# Sch1.net
KiCad netlist of a schematic drawn in EasyEDA Pro
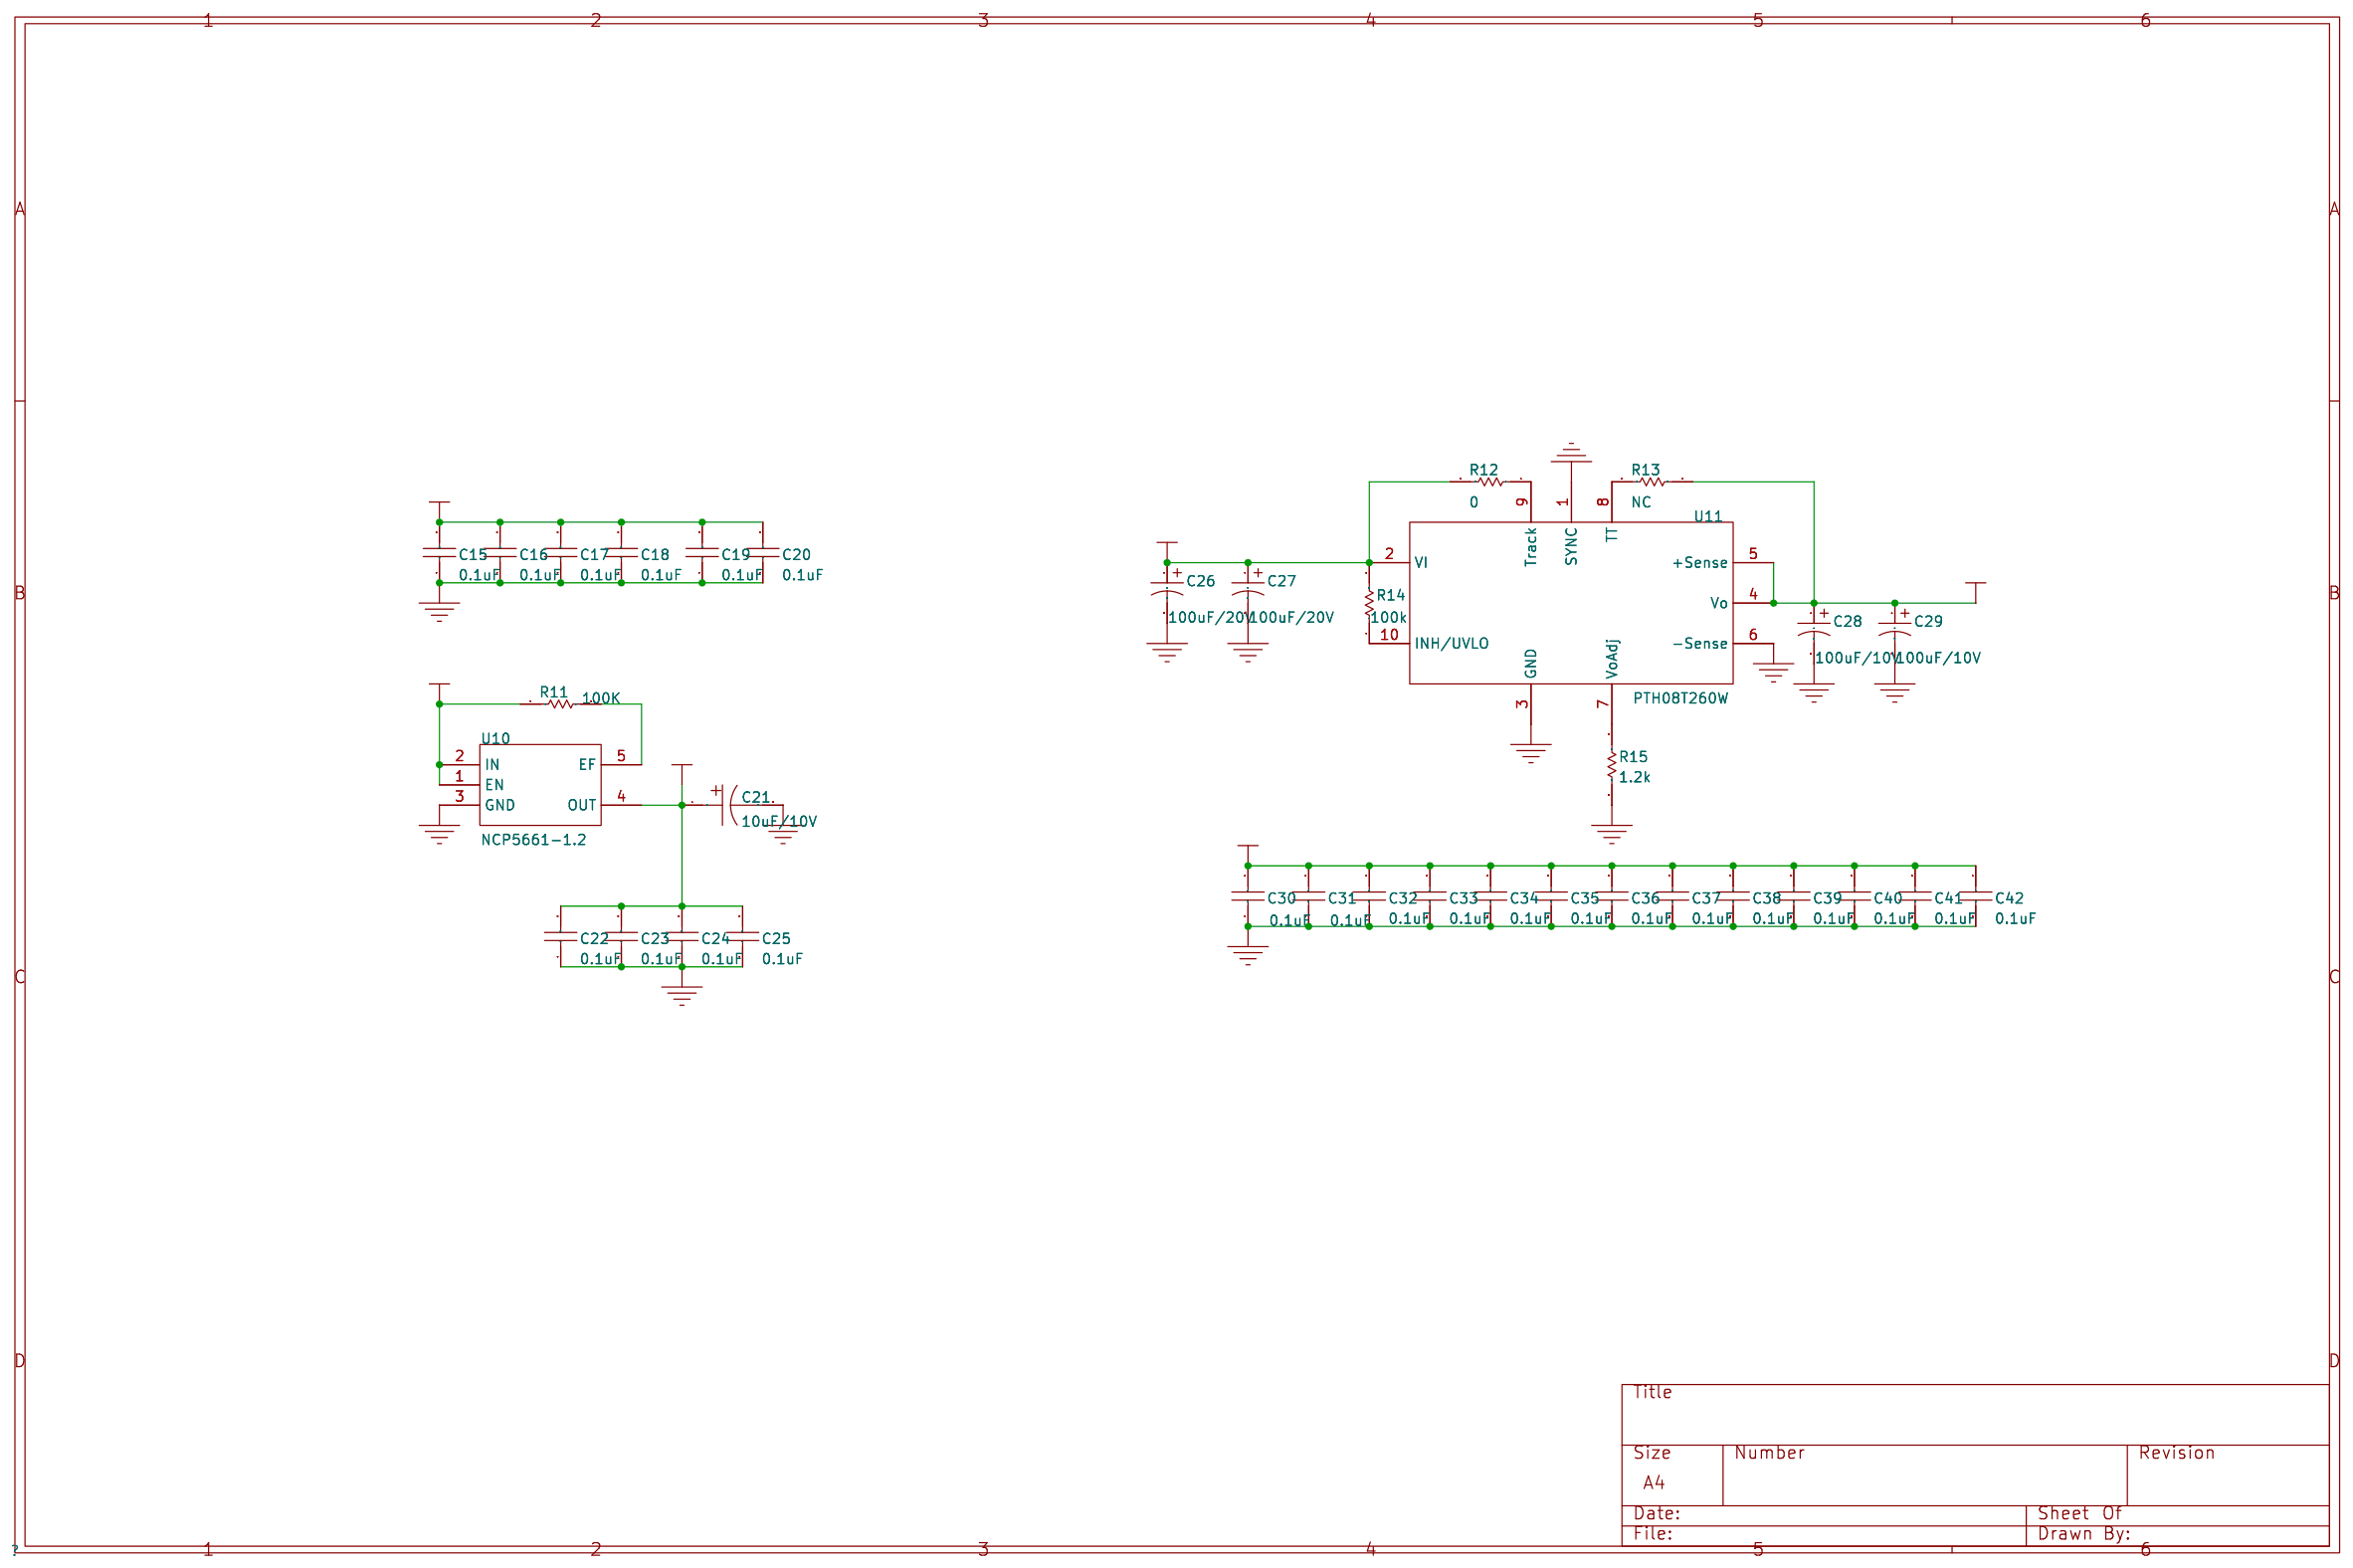
[diagram p0: 01-POWER]
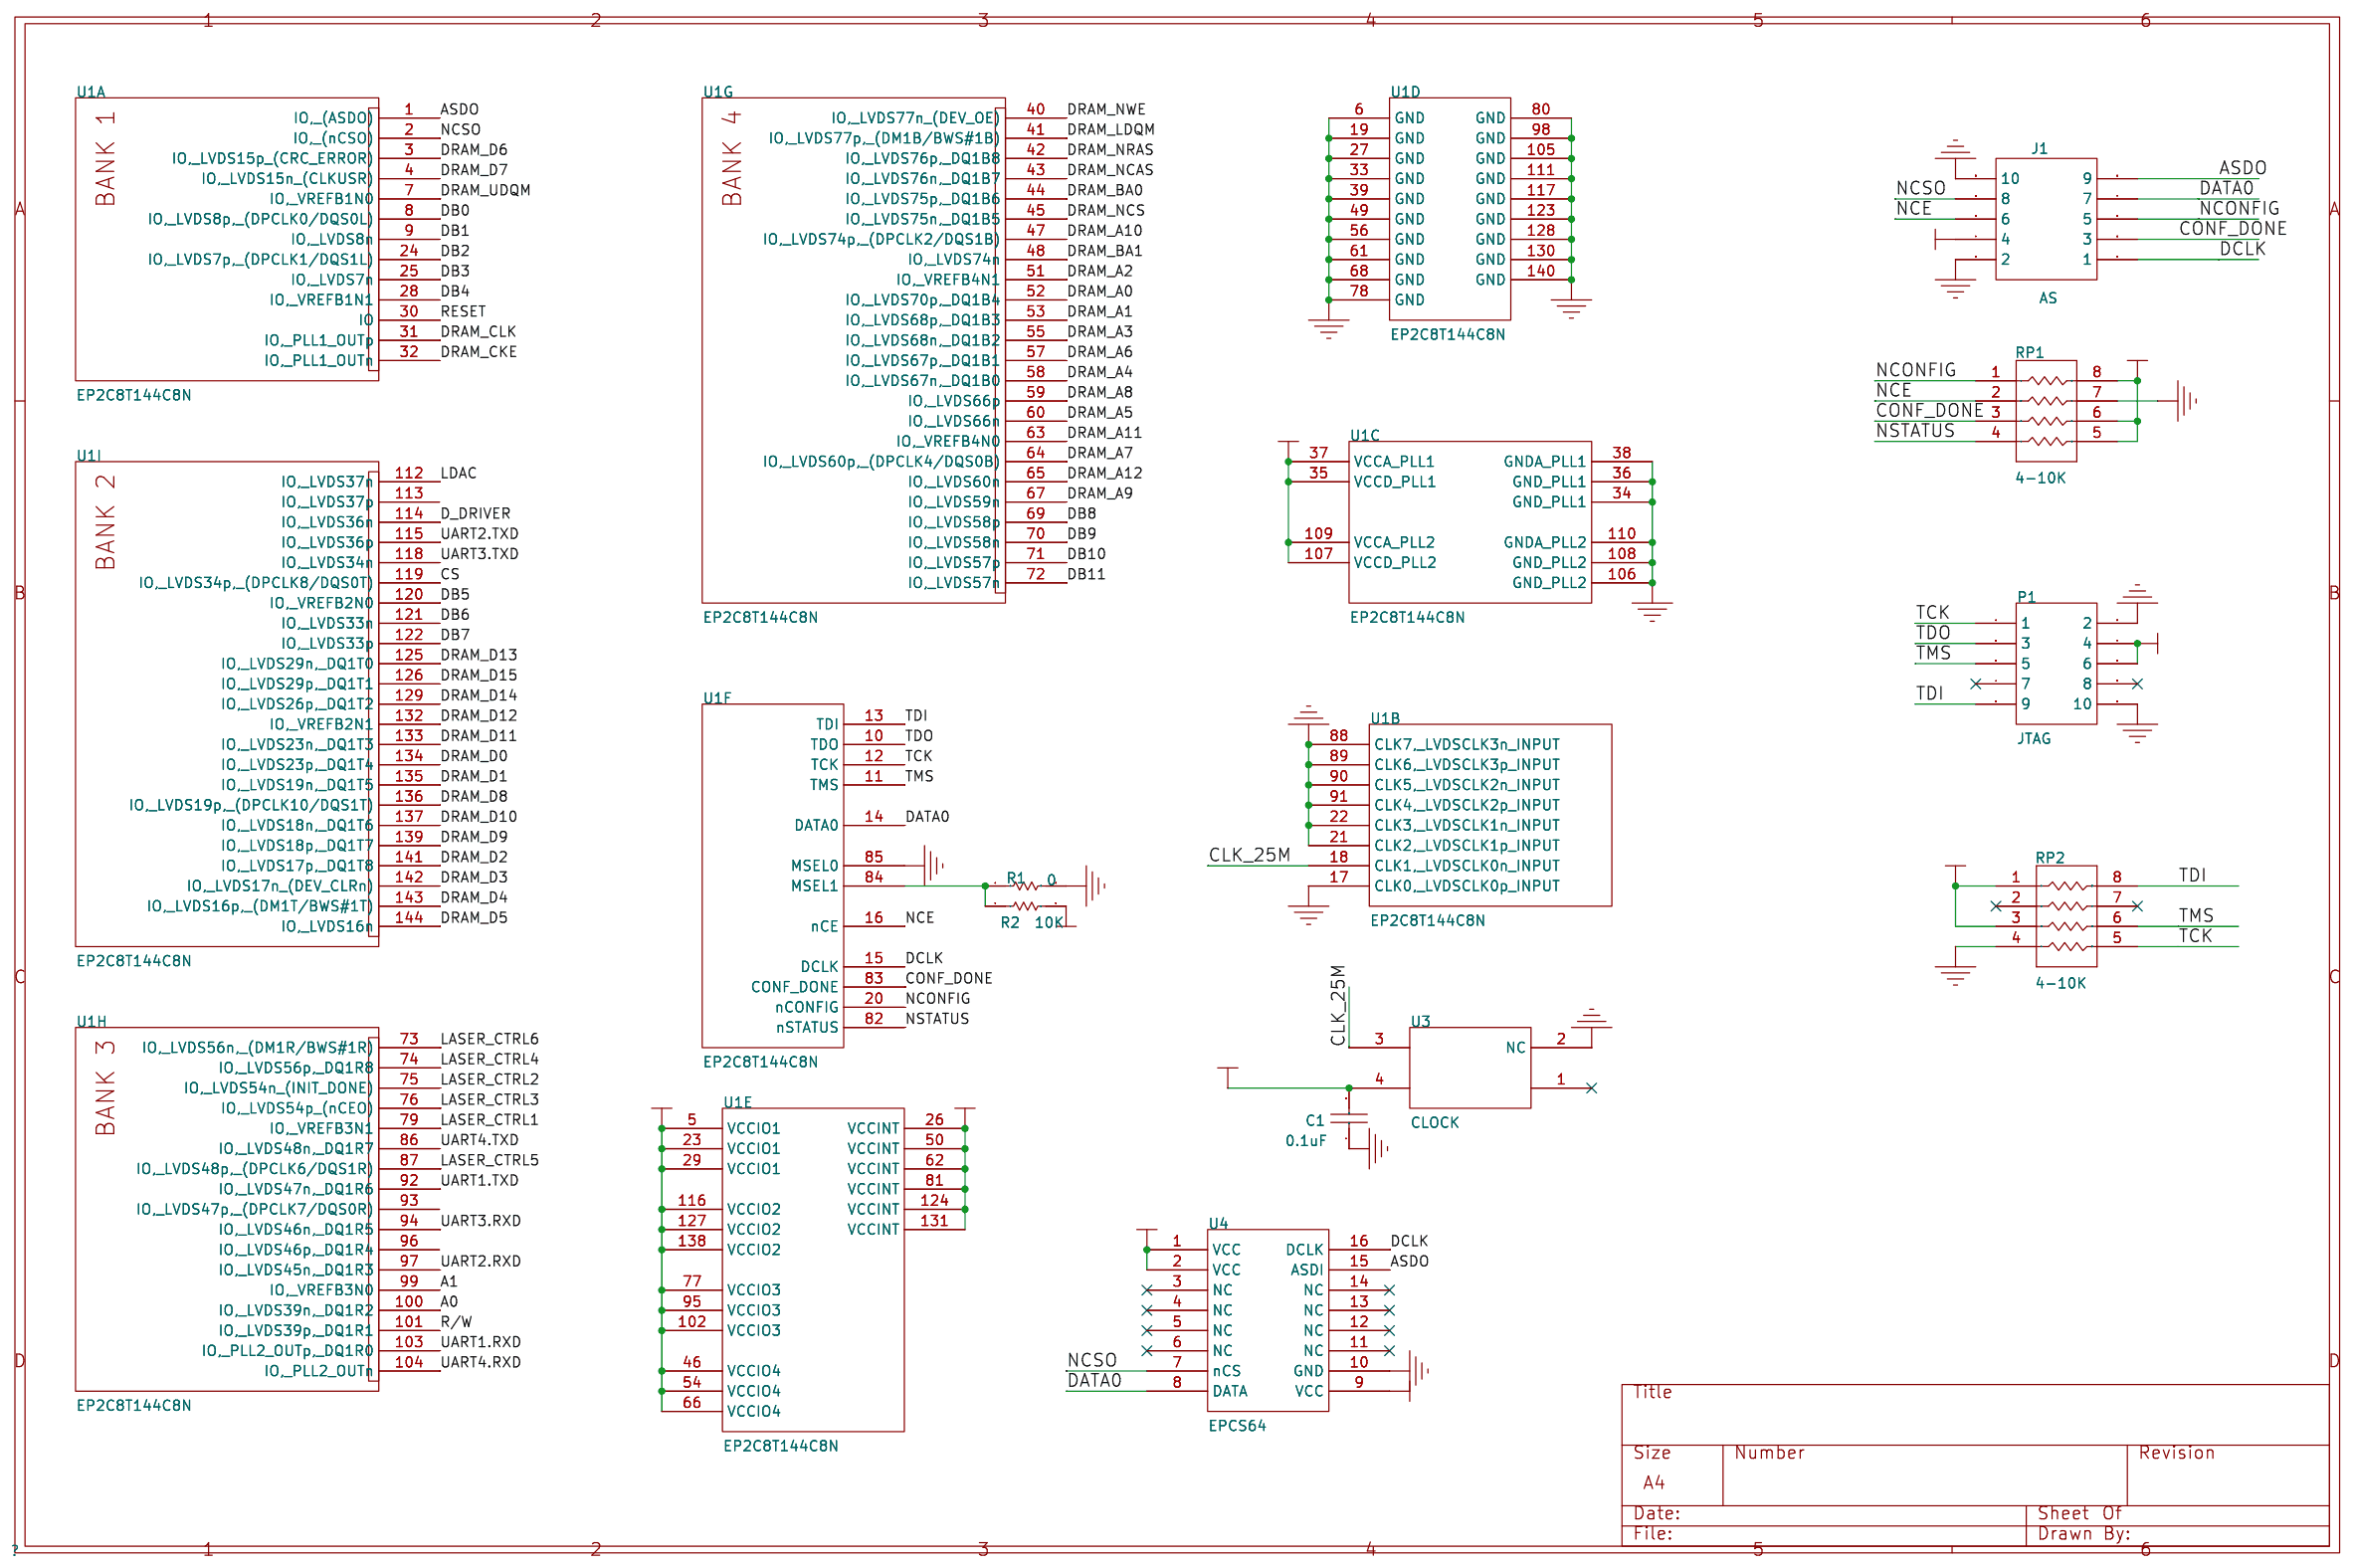
[diagram p1: 02-FPGA]
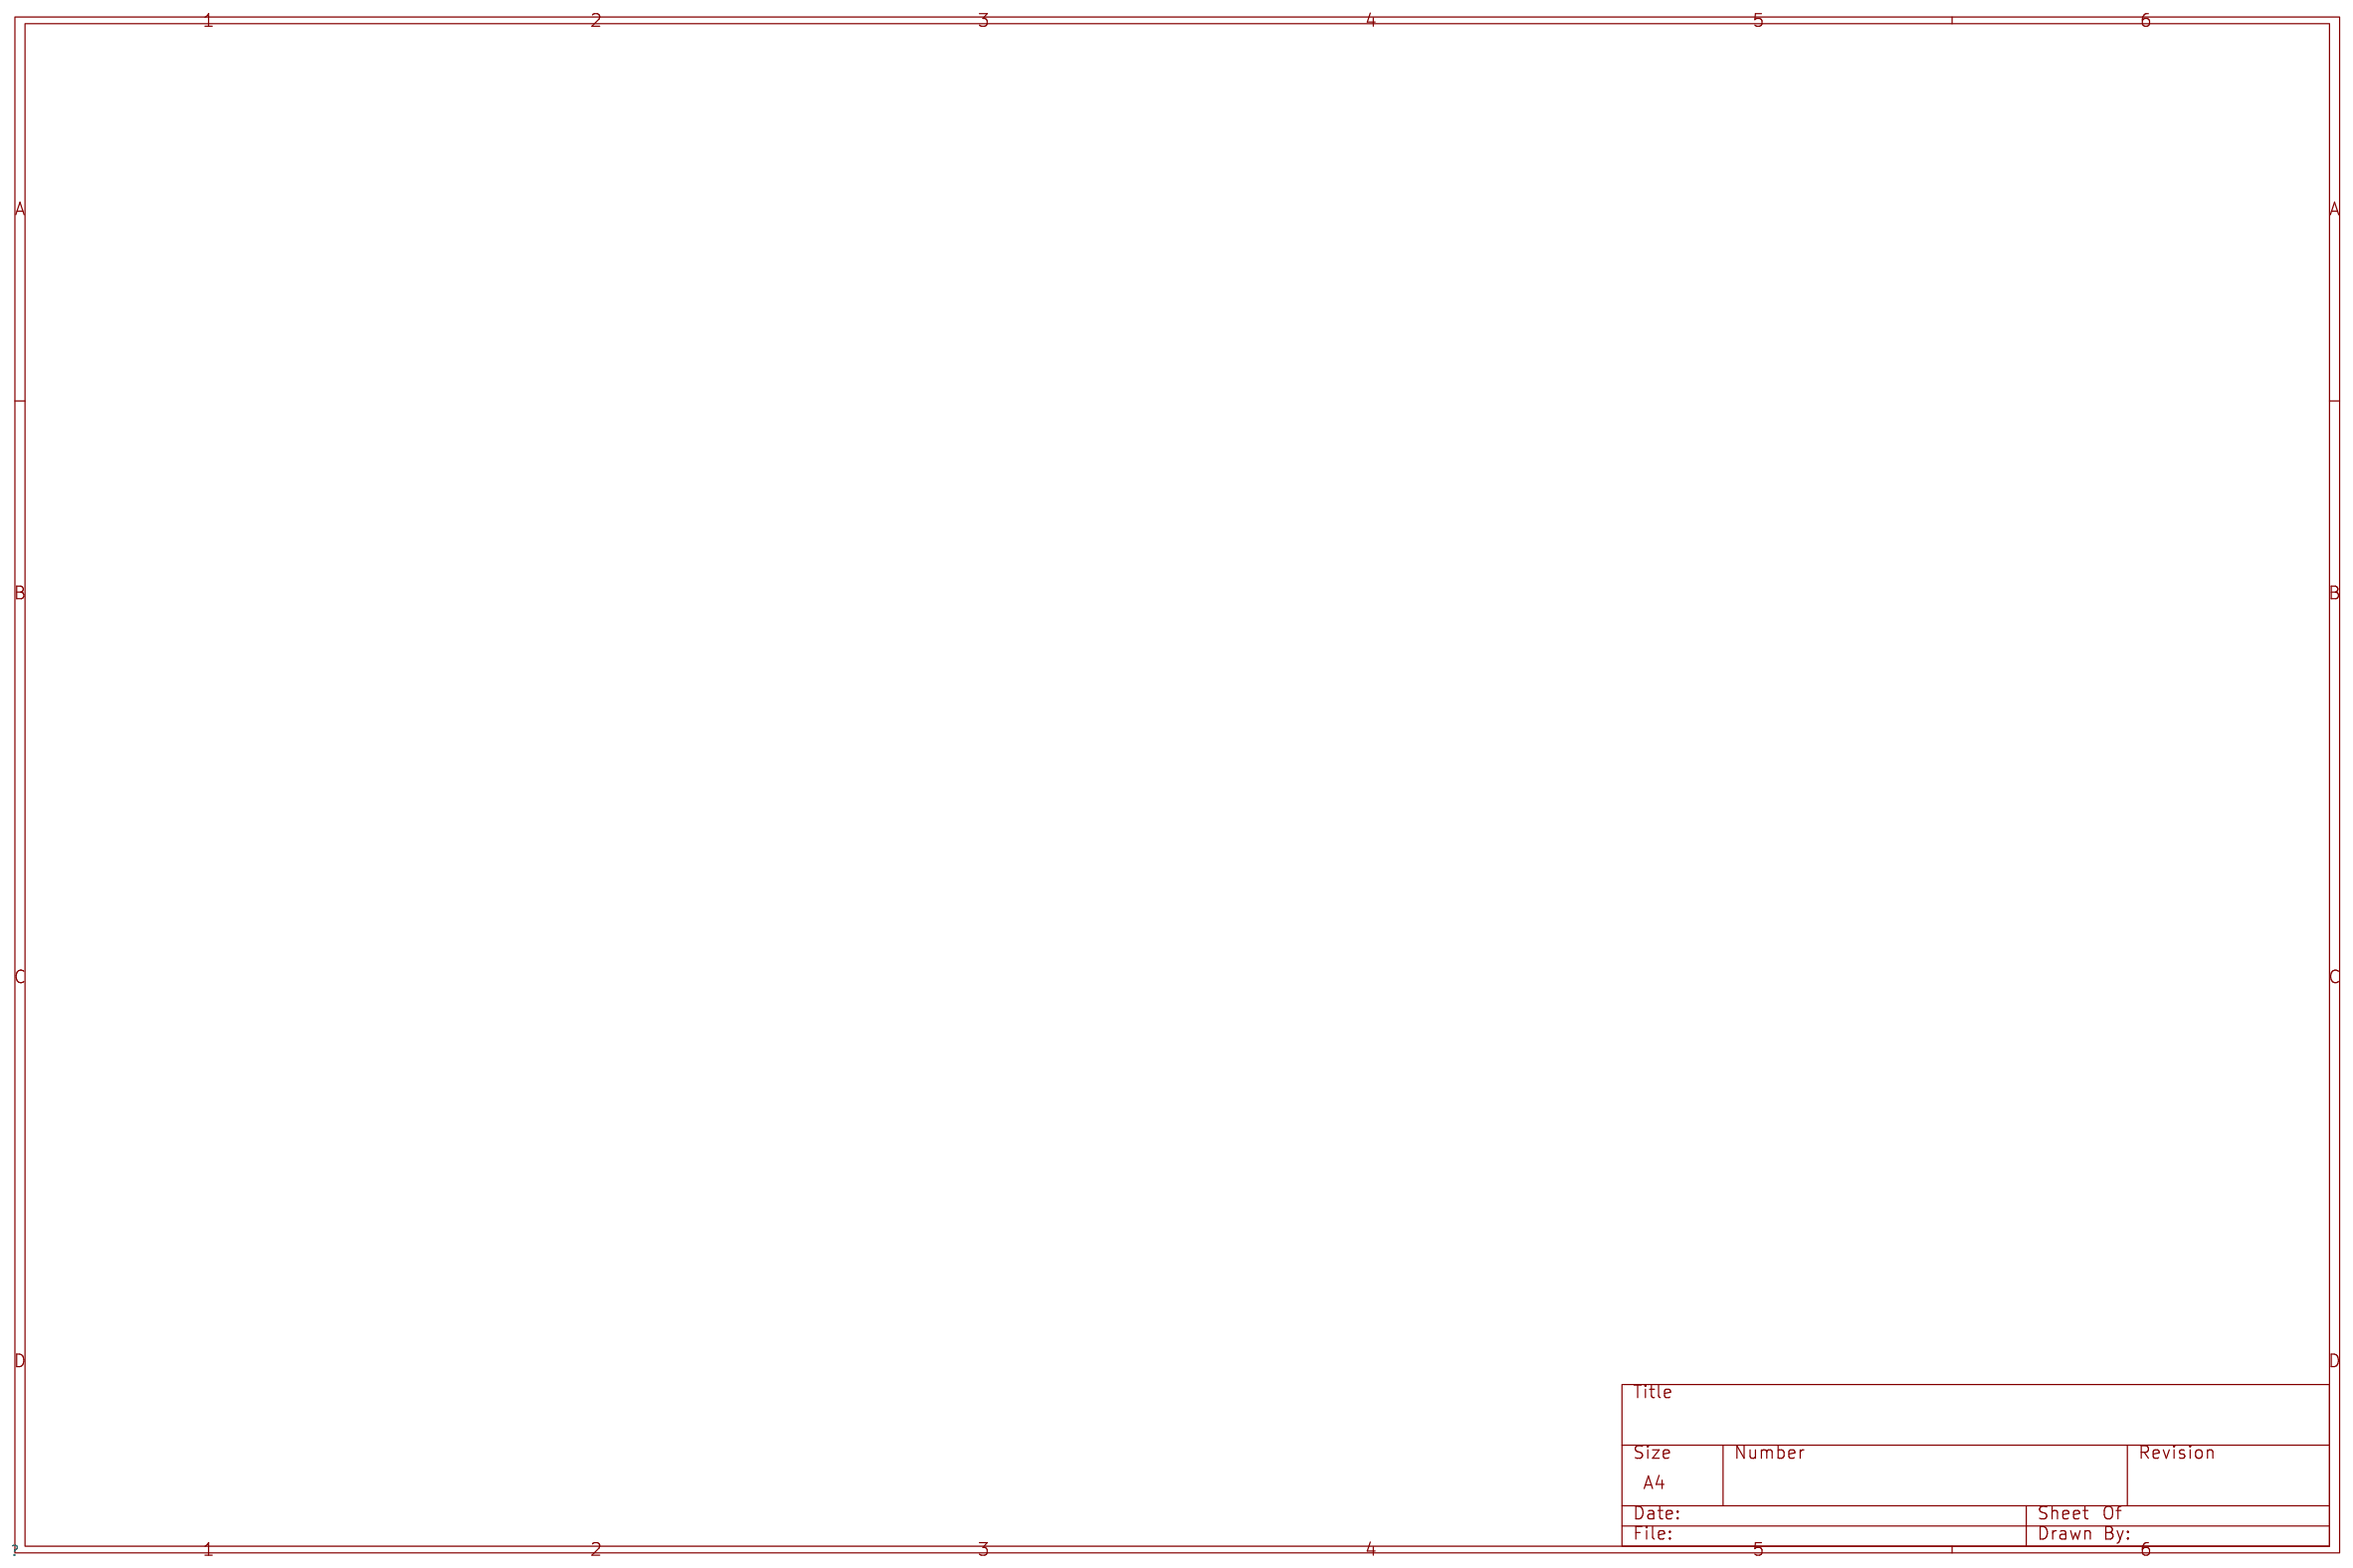
[diagram p2: 03-MEMORY]
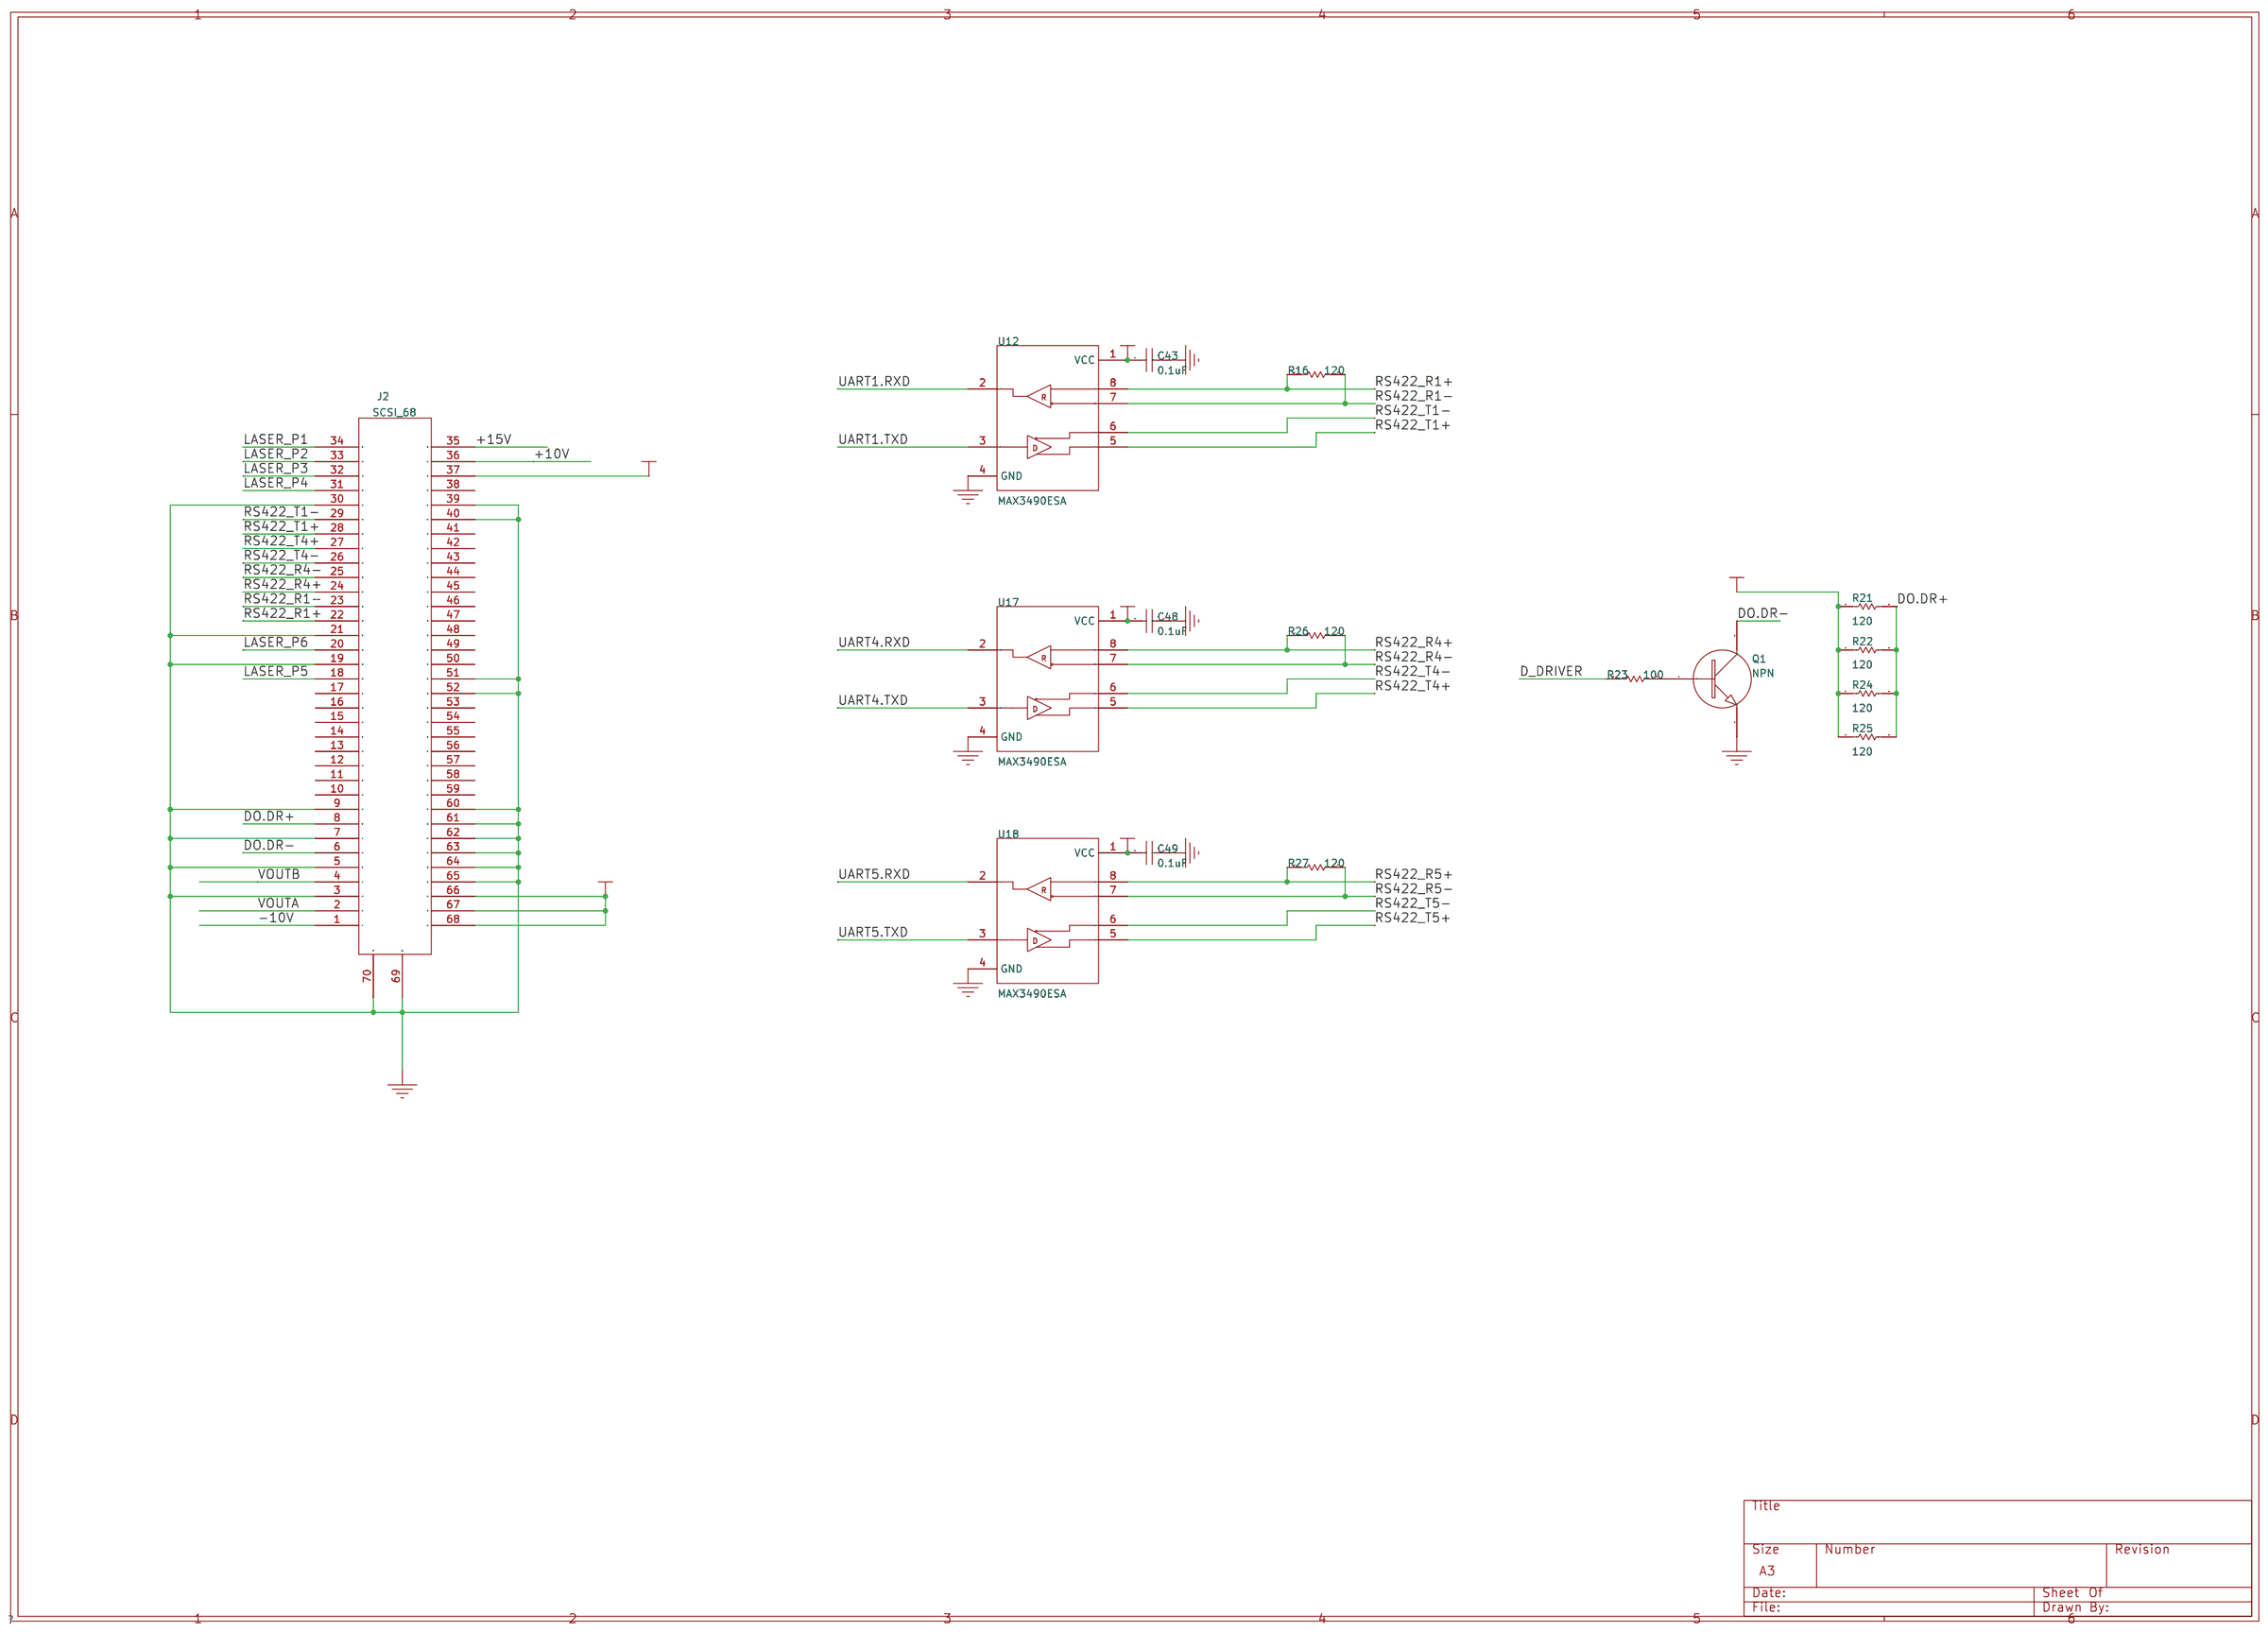
[diagram p3: 04-RS422-2]
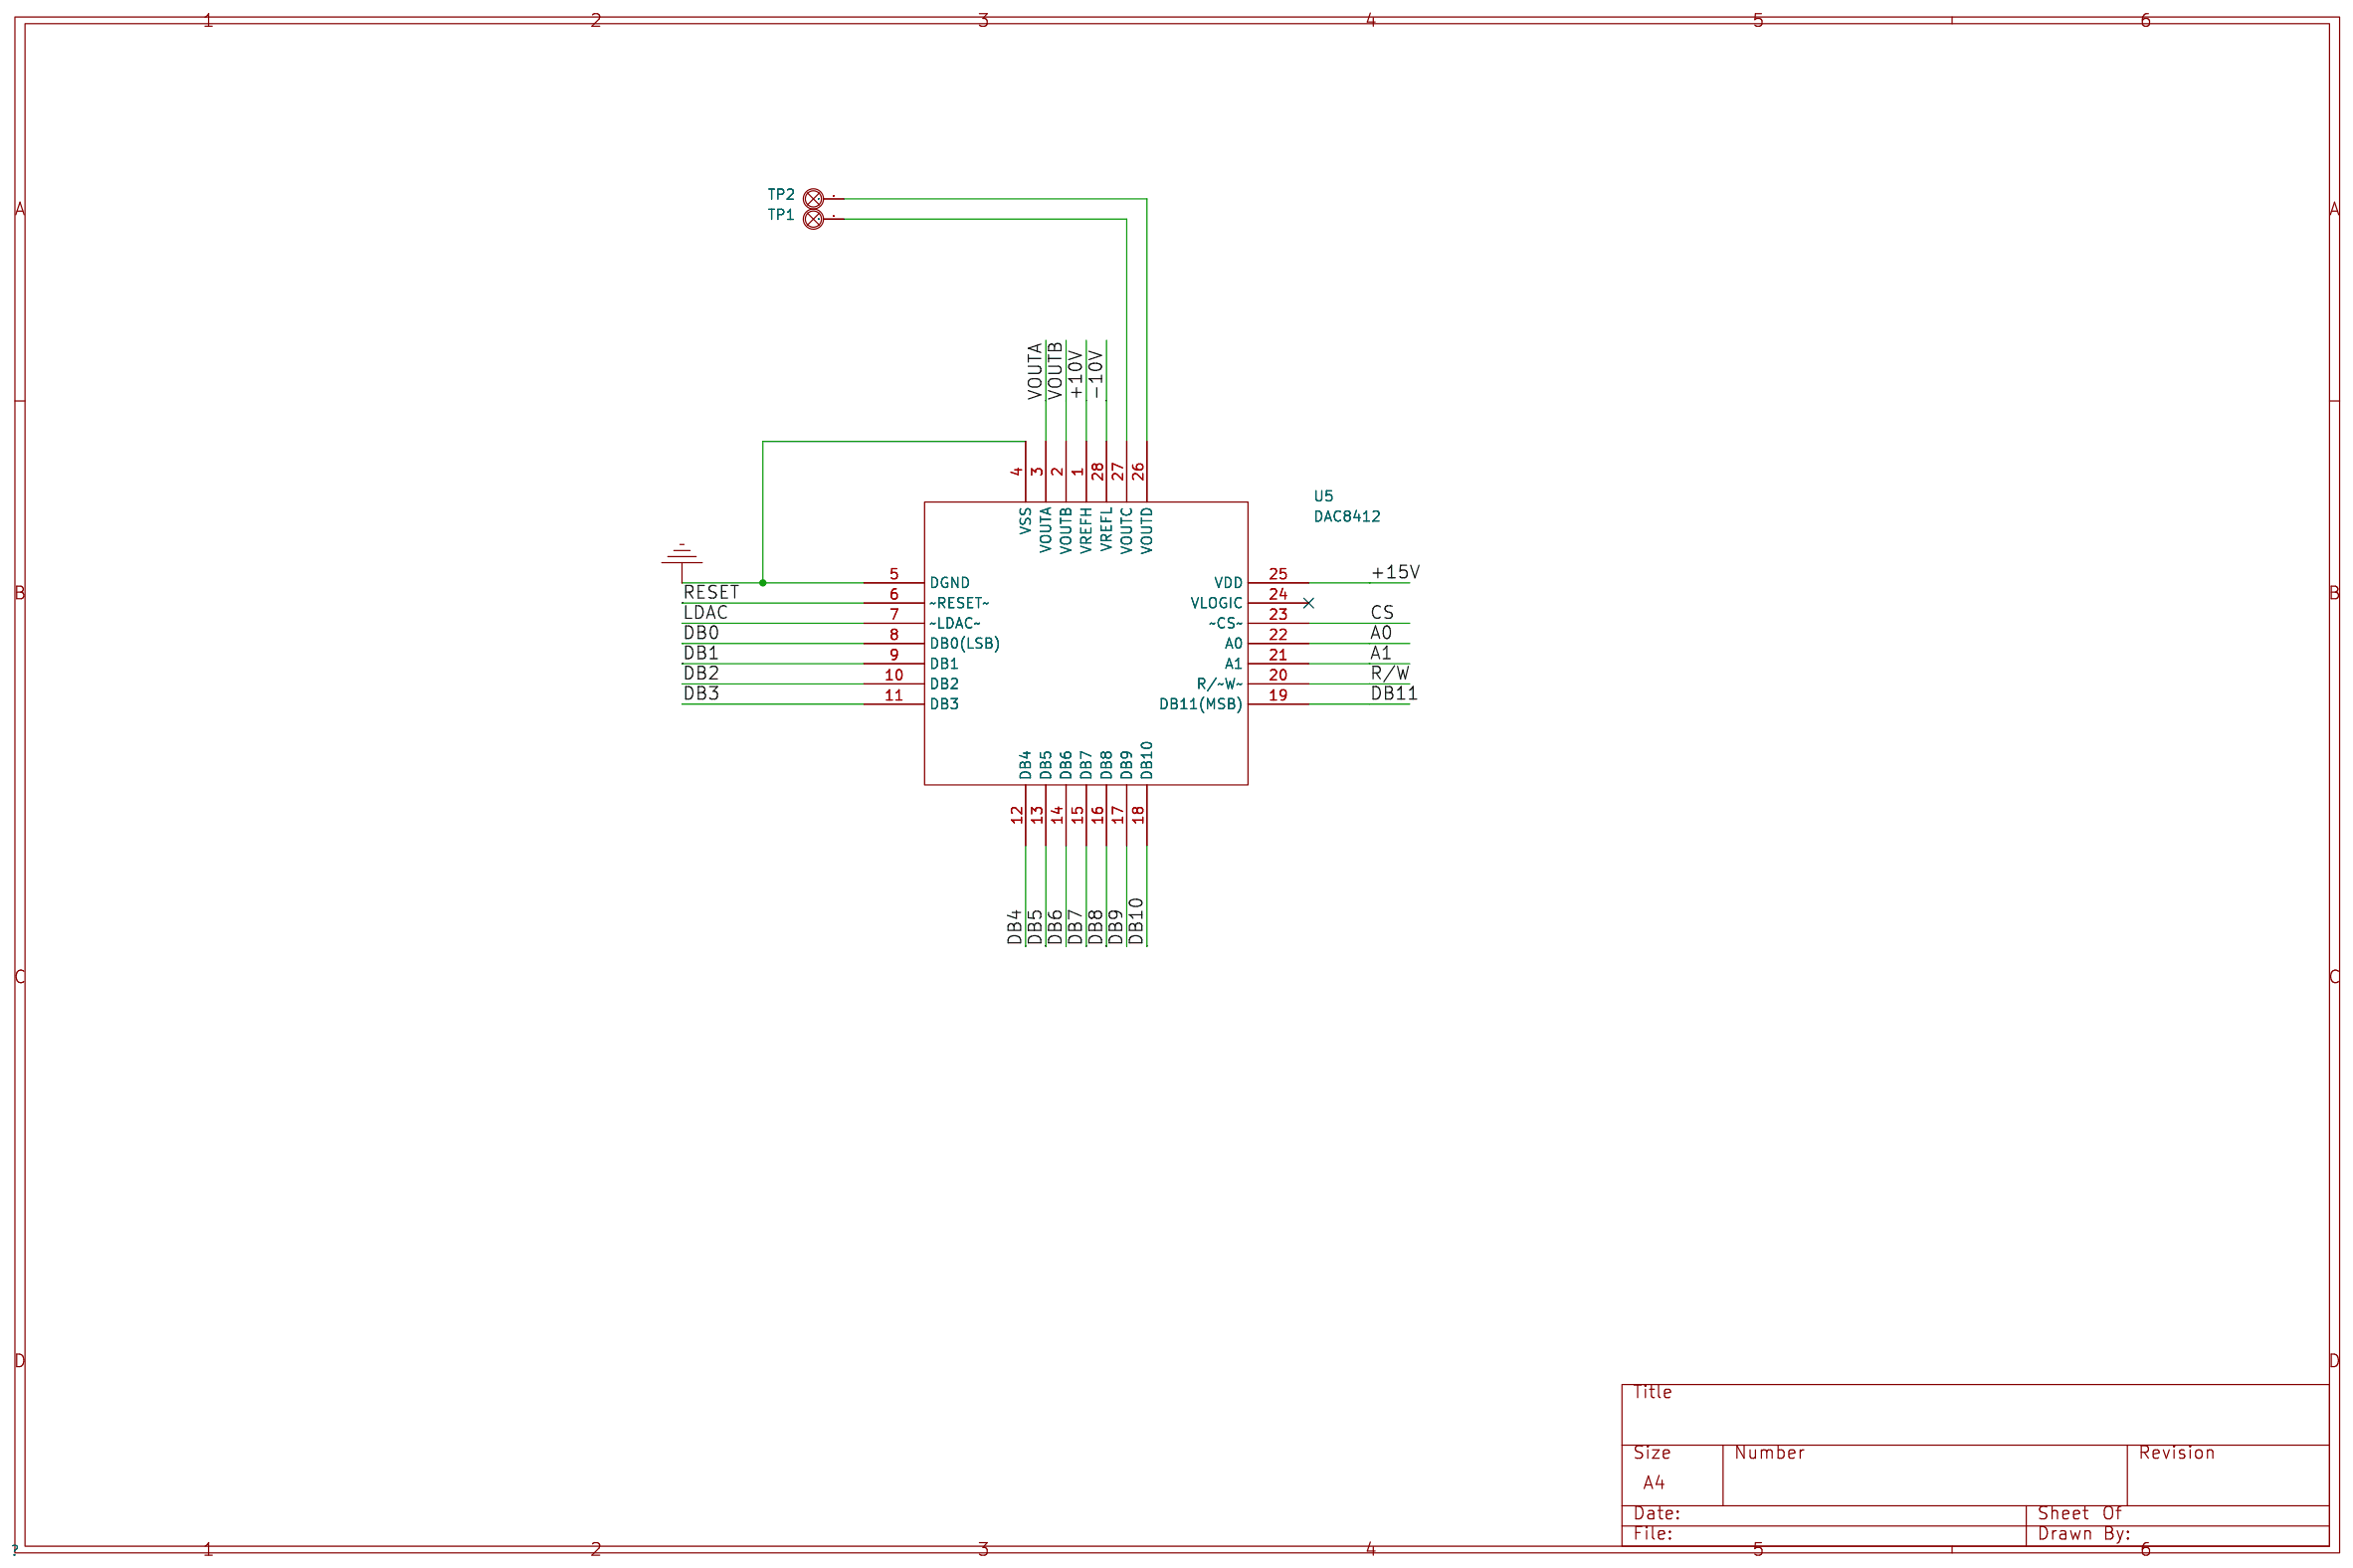
[diagram p4: 05-AD8412]
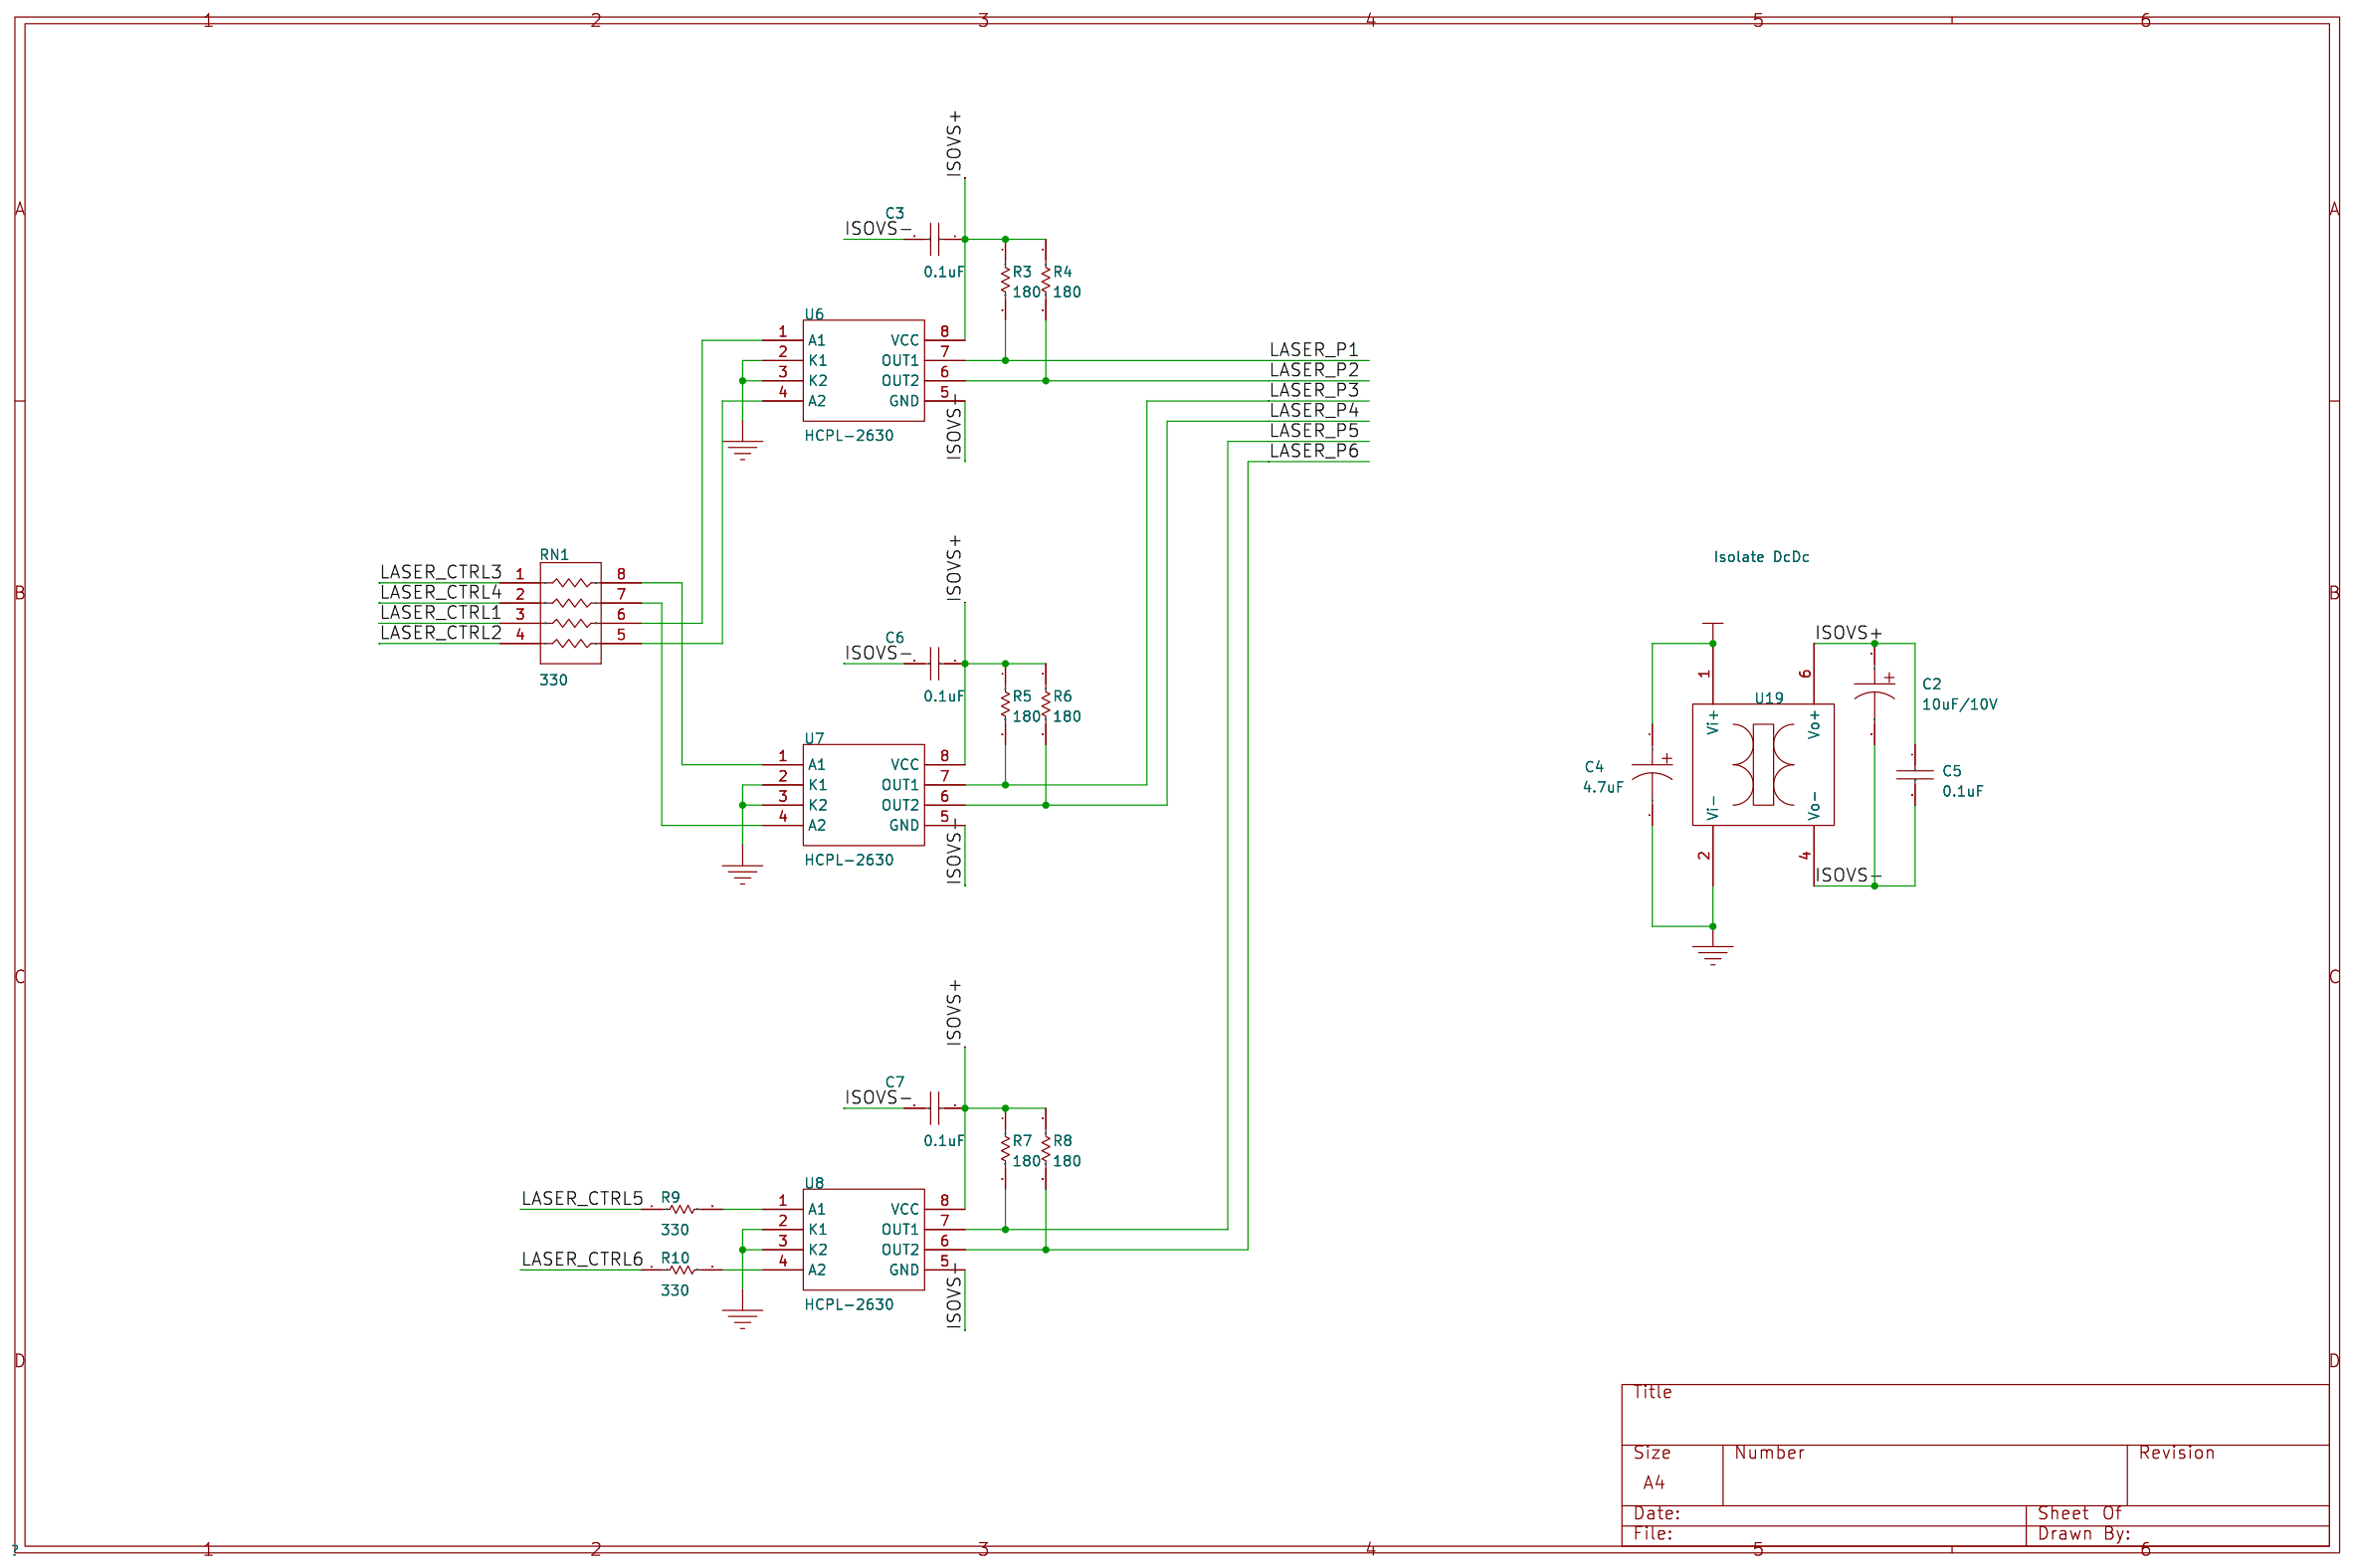
[diagram p5: 06-LASERCONTROL]

(export (version "E")
  (design (tool "Eeschema 10.0.6"))
  (components
    (comp (ref "C15")
      (value "0.1uF")
      (description "Capacitor")
      (fields (field (name "Publisher") "Altium Limited"))
      (libsource (lib "easyedapro") (part "Cap"))
    )
    (comp (ref "C16")
      (value "100pF")
      (description "Capacitor")
      (fields (field (name "Publisher") "Altium Limited"))
      (libsource (lib "easyedapro") (part "Cap"))
    )
    (comp (ref "C17")
      (value "100pF")
      (description "Capacitor")
      (fields (field (name "Publisher") "Altium Limited"))
      (libsource (lib "easyedapro") (part "Cap"))
    )
    (comp (ref "C18")
      (value "100pF")
      (description "Capacitor")
      (fields (field (name "Publisher") "Altium Limited"))
      (libsource (lib "easyedapro") (part "Cap"))
    )
    (comp (ref "C19")
      (value "100pF")
      (description "Capacitor")
      (fields (field (name "Publisher") "Altium Limited"))
      (libsource (lib "easyedapro") (part "Cap"))
    )
    (comp (ref "C20")
      (value "100pF")
      (description "Capacitor")
      (fields (field (name "Publisher") "Altium Limited"))
      (libsource (lib "easyedapro") (part "Cap"))
    )
    (comp (ref "C21")
      (value "10uF/10V")
      (description "Capacitor")
      (libsource (lib "easyedapro") (part "CAPACITOR POL"))
    )
    (comp (ref "C22")
      (value "0.1uF")
      (description "Capacitor (Semiconductor SIM Model)")
      (fields (field (name "Publisher") "Altium Limited"))
      (libsource (lib "easyedapro") (part "Cap Semi"))
    )
    (comp (ref "C23")
      (value "0.1uF")
      (description "Capacitor (Semiconductor SIM Model)")
      (fields (field (name "Publisher") "Altium Limited"))
      (libsource (lib "easyedapro") (part "Cap Semi"))
    )
    (comp (ref "C24")
      (value "0.1uF")
      (description "Capacitor (Semiconductor SIM Model)")
      (fields (field (name "Publisher") "Altium Limited"))
      (libsource (lib "easyedapro") (part "Cap Semi"))
    )
    (comp (ref "C25")
      (value "0.1uF")
      (description "Capacitor (Semiconductor SIM Model)")
      (fields (field (name "Publisher") "Altium Limited"))
      (libsource (lib "easyedapro") (part "Cap Semi"))
    )
    (comp (ref "C26")
      (value "100uF/20V")
      (description "钽电容,25V")
      (fields (field (name "Publisher") "Altium Limited"))
      (libsource (lib "easyedapro") (part "Cap Pol1"))
    )
    (comp (ref "C27")
      (value "100uF/20V")
      (description "钽电容,25V")
      (fields (field (name "Publisher") "Altium Limited"))
      (libsource (lib "easyedapro") (part "Cap Pol1"))
    )
    (comp (ref "C28")
      (value "100uF/10V")
      (description "10V, X7R")
      (fields (field (name "Publisher") "Altium Limited"))
      (libsource (lib "easyedapro") (part "Cap Pol1"))
    )
    (comp (ref "C29")
      (value "100uF/10V")
      (description "10V, X7R")
      (fields (field (name "Publisher") "Altium Limited"))
      (libsource (lib "easyedapro") (part "Cap Pol1"))
    )
    (comp (ref "C30")
      (value "0.1uF")
      (description "Capacitor (Semiconductor SIM Model)")
      (fields (field (name "Publisher") "Altium Limited"))
      (libsource (lib "easyedapro") (part "Cap Semi"))
    )
    (comp (ref "C31")
      (value "0.1uF")
      (description "Capacitor (Semiconductor SIM Model)")
      (fields (field (name "Publisher") "Altium Limited"))
      (libsource (lib "easyedapro") (part "Cap Semi"))
    )
    (comp (ref "C32")
      (value "0.1uF")
      (description "Capacitor (Semiconductor SIM Model)")
      (fields (field (name "Publisher") "Altium Limited"))
      (libsource (lib "easyedapro") (part "Cap Semi"))
    )
    (comp (ref "C33")
      (value "0.1uF")
      (description "Capacitor (Semiconductor SIM Model)")
      (fields (field (name "Publisher") "Altium Limited"))
      (libsource (lib "easyedapro") (part "Cap Semi"))
    )
    (comp (ref "C34")
      (value "0.1uF")
      (description "Capacitor (Semiconductor SIM Model)")
      (fields (field (name "Publisher") "Altium Limited"))
      (libsource (lib "easyedapro") (part "Cap Semi"))
    )
    (comp (ref "C35")
      (value "0.1uF")
      (description "Capacitor (Semiconductor SIM Model)")
      (fields (field (name "Publisher") "Altium Limited"))
      (libsource (lib "easyedapro") (part "Cap Semi"))
    )
    (comp (ref "C36")
      (value "0.1uF")
      (description "Capacitor (Semiconductor SIM Model)")
      (fields (field (name "Publisher") "Altium Limited"))
      (libsource (lib "easyedapro") (part "Cap Semi"))
    )
    (comp (ref "C37")
      (value "0.1uF")
      (description "Capacitor (Semiconductor SIM Model)")
      (fields (field (name "Publisher") "Altium Limited"))
      (libsource (lib "easyedapro") (part "Cap Semi"))
    )
    (comp (ref "C38")
      (value "0.1uF")
      (description "Capacitor (Semiconductor SIM Model)")
      (fields (field (name "Publisher") "Altium Limited"))
      (libsource (lib "easyedapro") (part "Cap Semi"))
    )
    (comp (ref "C39")
      (value "0.1uF")
      (description "Capacitor (Semiconductor SIM Model)")
      (fields (field (name "Publisher") "Altium Limited"))
      (libsource (lib "easyedapro") (part "Cap Semi"))
    )
    (comp (ref "C40")
      (value "0.1uF")
      (description "Capacitor (Semiconductor SIM Model)")
      (fields (field (name "Publisher") "Altium Limited"))
      (libsource (lib "easyedapro") (part "Cap Semi"))
    )
    (comp (ref "C41")
      (value "0.1uF")
      (description "Capacitor (Semiconductor SIM Model)")
      (fields (field (name "Publisher") "Altium Limited"))
      (libsource (lib "easyedapro") (part "Cap Semi"))
    )
    (comp (ref "C42")
      (value "0.1uF")
      (description "Capacitor (Semiconductor SIM Model)")
      (fields (field (name "Publisher") "Altium Limited"))
      (libsource (lib "easyedapro") (part "Cap Semi"))
    )
    (comp (ref "R11")
      (value "100K")
      (description "Semiconductor Resistor")
      (fields (field (name "Publisher") "Altium Limited"))
      (libsource (lib "easyedapro") (part "Res Semi"))
    )
    (comp (ref "R12")
      (value "0")
      (description "Resistor")
      (fields (field (name "Publisher") "Altium Limited"))
      (libsource (lib "easyedapro") (part "Res1"))
    )
    (comp (ref "R13")
      (value "NC")
      (description "Resistor")
      (fields (field (name "Publisher") "Altium Limited"))
      (libsource (lib "easyedapro") (part "Res1"))
    )
    (comp (ref "R14")
      (value "100k")
      (description "Resistor")
      (fields (field (name "Publisher") "Altium Limited"))
      (libsource (lib "easyedapro") (part "Res1"))
    )
    (comp (ref "R15")
      (value "1.2k")
      (description "Resistor")
      (fields (field (name "Publisher") "Altium Limited"))
      (libsource (lib "easyedapro") (part "Res1"))
    )
    (comp (ref "U10") (value "NCP5661-1.2") (libsource (lib "easyedapro") (part "NCP5661")))
    (comp (ref "U11")
      (value "PTH08T260W")
      (description "TI电源模块")
      (libsource (lib "easyedapro") (part "PTH08T230W"))
    )
    (comp (ref "C1") (value "0.1uF") (description "Capacitor") (libsource (lib "easyedapro") (part "CAP")))
    (comp (ref "J1") (value "AS") (libsource (lib "easyedapro") (part "HEADER 5X2")))
    (comp (ref "P1")
      (value "JTAG")
      (description "Header, 5-Pin, Dual row")
      (fields (field (name "Publisher") "Altium Limited"))
      (libsource (lib "easyedapro") (part "Header 5X2"))
    )
    (comp (ref "R1")
      (value "0")
      (description "Semiconductor Resistor")
      (fields (field (name "Publisher") "Altium Limited"))
      (libsource (lib "easyedapro") (part "Res Semi"))
    )
    (comp (ref "R2")
      (value "10K")
      (description "Semiconductor Resistor")
      (fields (field (name "Publisher") "Altium Limited"))
      (libsource (lib "easyedapro") (part "Res Semi"))
    )
    (comp (ref "RP1") (value "4-10K") (libsource (lib "easyedapro") (part "RES-4")))
    (comp (ref "RP2") (value "4-10K") (libsource (lib "easyedapro") (part "RES-4")))
    (comp (ref "U1")
      (value "EP2C8T144C8N")
      (fields (field (name "Publisher") "Altium Limited"))
      (libsource (lib "easyedapro") (part "EP2C8T144C8N"))
    )
    (comp (ref "U3") (value "CLOCK") (libsource (lib "easyedapro") (part "CLOCK")))
    (comp (ref "U4")
      (value "EPCS64")
      (description "EPCS16 64 128")
      (libsource (lib "easyedapro") (part "EPCS64"))
    )
    (comp (ref "C43")
      (value "0.1uF")
      (description "X7R")
      (fields (field (name "Publisher") "Altium Limited"))
      (libsource (lib "easyedapro") (part "Cap"))
    )
    (comp (ref "C48")
      (value "0.1uF")
      (description "X7R")
      (fields (field (name "Publisher") "Altium Limited"))
      (libsource (lib "easyedapro") (part "Cap"))
    )
    (comp (ref "C49")
      (value "0.1uF")
      (description "X7R")
      (fields (field (name "Publisher") "Altium Limited"))
      (libsource (lib "easyedapro") (part "Cap"))
    )
    (comp (ref "J2") (value "SCSI_68") (libsource (lib "easyedapro") (part "SCSI68")))
    (comp (ref "Q1") (value "NPN") (description "NPN Transistor") (libsource (lib "easyedapro") (part "NPN")))
    (comp (ref "R16")
      (value "120")
      (description "Resistor")
      (fields (field (name "Publisher") "Altium Limited"))
      (libsource (lib "easyedapro") (part "Res1"))
    )
    (comp (ref "R21")
      (value "120")
      (description "Resistor")
      (fields (field (name "Publisher") "Altium Limited"))
      (libsource (lib "easyedapro") (part "Res1"))
    )
    (comp (ref "R22")
      (value "120")
      (description "Resistor")
      (fields (field (name "Publisher") "Altium Limited"))
      (libsource (lib "easyedapro") (part "Res1"))
    )
    (comp (ref "R23")
      (value "100")
      (description "Resistor")
      (fields (field (name "Publisher") "Altium Limited"))
      (libsource (lib "easyedapro") (part "Res1"))
    )
    (comp (ref "R24")
      (value "120")
      (description "Resistor")
      (fields (field (name "Publisher") "Altium Limited"))
      (libsource (lib "easyedapro") (part "Res1"))
    )
    (comp (ref "R25")
      (value "120")
      (description "Resistor")
      (fields (field (name "Publisher") "Altium Limited"))
      (libsource (lib "easyedapro") (part "Res1"))
    )
    (comp (ref "R26")
      (value "120")
      (description "Resistor")
      (fields (field (name "Publisher") "Altium Limited"))
      (libsource (lib "easyedapro") (part "Res1"))
    )
    (comp (ref "R27")
      (value "120")
      (description "Resistor")
      (fields (field (name "Publisher") "Altium Limited"))
      (libsource (lib "easyedapro") (part "Res1"))
    )
    (comp (ref "U12")
      (value "MAX3490ESA")
      (description "Low-Power, Slew-Rate-Limited RS-485/RS-422 Transceiver")
      (fields (field (name "Publisher") "Altium Limited"))
      (libsource (lib "easyedapro") (part "MAX488ESA"))
    )
    (comp (ref "U17")
      (value "MAX3490ESA")
      (description "Low-Power, Slew-Rate-Limited RS-485/RS-422 Transceiver")
      (fields (field (name "Publisher") "Altium Limited"))
      (libsource (lib "easyedapro") (part "MAX488ESA"))
    )
    (comp (ref "U18")
      (value "MAX3490ESA")
      (description "Low-Power, Slew-Rate-Limited RS-485/RS-422 Transceiver")
      (fields (field (name "Publisher") "Altium Limited"))
      (libsource (lib "easyedapro") (part "MAX488ESA"))
    )
    (comp (ref "TP1") (value "TESTPOINT") (libsource (lib "easyedapro") (part "TESTPOINT_0")))
    (comp (ref "TP2") (value "TESTPOINT") (libsource (lib "easyedapro") (part "TESTPOINT_0")))
    (comp (ref "U5") (value "DAC8412") (libsource (lib "easyedapro") (part "DAC8412")))
    (comp (ref "C2")
      (value "10uF/10V")
      (description "Capacitor")
      (libsource (lib "easyedapro") (part "CAPACITOR POL"))
    )
    (comp (ref "C3")
      (value "100pF")
      (description "Capacitor")
      (fields (field (name "Publisher") "Altium Limited"))
      (libsource (lib "easyedapro") (part "Cap"))
    )
    (comp (ref "C4")
      (value "4.7uF")
      (description "Capacitor")
      (libsource (lib "easyedapro") (part "CAPACITOR POL"))
    )
    (comp (ref "C5") (value "0.1uF") (description "Capacitor") (libsource (lib "easyedapro") (part "CAP")))
    (comp (ref "C6")
      (value "100pF")
      (description "Capacitor")
      (fields (field (name "Publisher") "Altium Limited"))
      (libsource (lib "easyedapro") (part "Cap"))
    )
    (comp (ref "C7")
      (value "100pF")
      (description "Capacitor")
      (fields (field (name "Publisher") "Altium Limited"))
      (libsource (lib "easyedapro") (part "Cap"))
    )
    (comp (ref "R3")
      (value "1K")
      (description "Resistor")
      (fields (field (name "Publisher") "Altium Limited"))
      (libsource (lib "easyedapro") (part "Res1"))
    )
    (comp (ref "R4")
      (value "1K")
      (description "Resistor")
      (fields (field (name "Publisher") "Altium Limited"))
      (libsource (lib "easyedapro") (part "Res1"))
    )
    (comp (ref "R5")
      (value "1K")
      (description "Resistor")
      (fields (field (name "Publisher") "Altium Limited"))
      (libsource (lib "easyedapro") (part "Res1"))
    )
    (comp (ref "R6")
      (value "1K")
      (description "Resistor")
      (fields (field (name "Publisher") "Altium Limited"))
      (libsource (lib "easyedapro") (part "Res1"))
    )
    (comp (ref "R7")
      (value "1K")
      (description "Resistor")
      (fields (field (name "Publisher") "Altium Limited"))
      (libsource (lib "easyedapro") (part "Res1"))
    )
    (comp (ref "R8")
      (value "1K")
      (description "Resistor")
      (fields (field (name "Publisher") "Altium Limited"))
      (libsource (lib "easyedapro") (part "Res1"))
    )
    (comp (ref "R9")
      (value "1K")
      (description "Resistor")
      (fields (field (name "Publisher") "Altium Limited"))
      (libsource (lib "easyedapro") (part "Res1"))
    )
    (comp (ref "R10")
      (value "1K")
      (description "Resistor")
      (fields (field (name "Publisher") "Altium Limited"))
      (libsource (lib "easyedapro") (part "Res1"))
    )
    (comp (ref "RN1")
      (value "330")
      (description "Resistor Array,include 4 resistor in one chip")
      (libsource (lib "easyedapro") (part "RN4"))
    )
    (comp (ref "U6") (value "HCPL-2630") (libsource (lib "easyedapro") (part "HCPL-2630")))
    (comp (ref "U7") (value "HCPL-2630") (libsource (lib "easyedapro") (part "HCPL-2630")))
    (comp (ref "U8") (value "HCPL-2630") (libsource (lib "easyedapro") (part "HCPL-2630")))
    (comp (ref "U19") (value "Isolate DcDc") (libsource (lib "easyedapro") (part "MY_I_DC_DC")))
  )
  (nets
    (net (code "1") (name "+10V") (class "Default")
      (node (ref "J2") (pin "36") (pinfunction "36_36") (pintype "unspecified"))
      (node (ref "U5") (pin "1") (pinfunction "VREFH_1") (pintype "unspecified"))
    )
    (net (code "2") (name "+15V") (class "Default")
      (node (ref "J2") (pin "35") (pinfunction "35_35") (pintype "unspecified"))
      (node (ref "U5") (pin "25") (pinfunction "VDD_25") (pintype "unspecified"))
    )
    (net (code "3") (name "-10V") (class "Default")
      (node (ref "J2") (pin "1") (pinfunction "1_1") (pintype "unspecified"))
      (node (ref "U5") (pin "28") (pinfunction "VREFL_28") (pintype "unspecified"))
    )
    (net (code "4") (name "A0") (class "Default")
      (node (ref "U1") (pin "100") (pinfunction "IO,_LVDS39n,_DQ1R2_100") (pintype "bidirectional"))
      (node (ref "U5") (pin "22") (pinfunction "A0_22") (pintype "unspecified"))
    )
    (net (code "5") (name "A1") (class "Default")
      (node (ref "U1") (pin "99") (pinfunction "IO,_VREFB3N0_99") (pintype "bidirectional"))
      (node (ref "U5") (pin "21") (pinfunction "A1_21") (pintype "unspecified"))
    )
    (net (code "6") (name "ASDO") (class "Default")
      (node (ref "J1") (pin "9") (pinfunction "9_9") (pintype "unspecified"))
      (node (ref "U1") (pin "1") (pinfunction "IO,_(ASDO)_1") (pintype "bidirectional"))
      (node (ref "U4") (pin "15") (pinfunction "ASDI_15") (pintype "unspecified"))
    )
    (net (code "7") (name "CLK_25M") (class "Default")
      (node (ref "U1") (pin "18") (pinfunction "CLK1,_LVDSCLK0n_INPUT_18") (pintype "input"))
      (node (ref "U3") (pin "3") (pintype "unspecified"))
    )
    (net (code "8") (name "CONF_DONE") (class "Default")
      (node (ref "J1") (pin "3") (pinfunction "3_3") (pintype "unspecified"))
      (node (ref "RP1") (pin "3") (pinfunction "3_3") (pintype "unspecified"))
      (node (ref "U1") (pin "83") (pinfunction "CONF_DONE_83") (pintype "bidirectional"))
    )
    (net (code "9") (name "CS") (class "Default")
      (node (ref "U1") (pin "119") (pinfunction "IO,_LVDS34p,_(DPCLK8/DQS0T)_119") (pintype "bidirectional"))
      (node (ref "U5") (pin "23") (pinfunction "~CS~_23") (pintype "unspecified"))
    )
    (net (code "10") (name "DATA0") (class "Default")
      (node (ref "J1") (pin "7") (pinfunction "7_7") (pintype "unspecified"))
      (node (ref "U1") (pin "14") (pinfunction "DATA0_14") (pintype "input"))
      (node (ref "U4") (pin "8") (pinfunction "DATA_8") (pintype "unspecified"))
    )
    (net (code "11") (name "DB0") (class "Default")
      (node (ref "U1") (pin "8") (pinfunction "IO,_LVDS8p,_(DPCLK0/DQS0L)_8") (pintype "bidirectional"))
      (node (ref "U5") (pin "8") (pinfunction "DB0(LSB)_8") (pintype "unspecified"))
    )
    (net (code "12") (name "DB1") (class "Default")
      (node (ref "U1") (pin "9") (pinfunction "IO,_LVDS8n_9") (pintype "bidirectional"))
      (node (ref "U5") (pin "9") (pinfunction "DB1_9") (pintype "unspecified"))
    )
    (net (code "13") (name "DB2") (class "Default")
      (node (ref "U1") (pin "24") (pinfunction "IO,_LVDS7p,_(DPCLK1/DQS1L)_24") (pintype "bidirectional"))
      (node (ref "U5") (pin "10") (pinfunction "DB2_10") (pintype "unspecified"))
    )
    (net (code "14") (name "DB3") (class "Default")
      (node (ref "U1") (pin "25") (pinfunction "IO,_LVDS7n_25") (pintype "bidirectional"))
      (node (ref "U5") (pin "11") (pinfunction "DB3_11") (pintype "unspecified"))
    )
    (net (code "15") (name "DB4") (class "Default")
      (node (ref "U1") (pin "28") (pinfunction "IO,_VREFB1N1_28") (pintype "bidirectional"))
      (node (ref "U5") (pin "12") (pinfunction "DB4_12") (pintype "unspecified"))
    )
    (net (code "16") (name "DB5") (class "Default")
      (node (ref "U1") (pin "120") (pinfunction "IO,_VREFB2N0_120") (pintype "bidirectional"))
      (node (ref "U5") (pin "13") (pinfunction "DB5_13") (pintype "unspecified"))
    )
    (net (code "17") (name "DB6") (class "Default")
      (node (ref "U1") (pin "121") (pinfunction "IO,_LVDS33n_121") (pintype "bidirectional"))
      (node (ref "U5") (pin "14") (pinfunction "DB6_14") (pintype "unspecified"))
    )
    (net (code "18") (name "DB7") (class "Default")
      (node (ref "U1") (pin "122") (pinfunction "IO,_LVDS33p_122") (pintype "bidirectional"))
      (node (ref "U5") (pin "15") (pinfunction "DB7_15") (pintype "unspecified"))
    )
    (net (code "19") (name "DB8") (class "Default")
      (node (ref "U1") (pin "69") (pinfunction "IO,_LVDS58p_69") (pintype "bidirectional"))
      (node (ref "U5") (pin "16") (pinfunction "DB8_16") (pintype "unspecified"))
    )
    (net (code "20") (name "DB9") (class "Default")
      (node (ref "U1") (pin "70") (pinfunction "IO,_LVDS58n_70") (pintype "bidirectional"))
      (node (ref "U5") (pin "17") (pinfunction "DB9_17") (pintype "unspecified"))
    )
    (net (code "21") (name "DB10") (class "Default")
      (node (ref "U1") (pin "71") (pinfunction "IO,_LVDS57p_71") (pintype "bidirectional"))
      (node (ref "U5") (pin "18") (pinfunction "DB10_18") (pintype "unspecified"))
    )
    (net (code "22") (name "DB11") (class "Default")
      (node (ref "U1") (pin "72") (pinfunction "IO,_LVDS57n_72") (pintype "bidirectional"))
      (node (ref "U5") (pin "19") (pinfunction "DB11(MSB)_19") (pintype "unspecified"))
    )
    (net (code "23") (name "DCLK") (class "Default")
      (node (ref "J1") (pin "1") (pinfunction "1_1") (pintype "unspecified"))
      (node (ref "U1") (pin "15") (pinfunction "DCLK_15") (pintype "bidirectional"))
      (node (ref "U4") (pin "16") (pinfunction "DCLK_16") (pintype "unspecified"))
    )
    (net (code "24") (name "DGND") (class "Default")
      (node (ref "C1") (pin "1") (pinfunction "1_1") (pintype "unspecified"))
      (node (ref "C15") (pin "1") (pinfunction "1_1") (pintype "unspecified"))
      (node (ref "C16") (pin "1") (pinfunction "1_1") (pintype "unspecified"))
      (node (ref "C17") (pin "1") (pinfunction "1_1") (pintype "unspecified"))
      (node (ref "C18") (pin "1") (pinfunction "1_1") (pintype "unspecified"))
      (node (ref "C19") (pin "1") (pinfunction "1_1") (pintype "unspecified"))
      (node (ref "C20") (pin "1") (pinfunction "1_1") (pintype "unspecified"))
      (node (ref "C21") (pin "2") (pinfunction "2_2") (pintype "unspecified"))
      (node (ref "C22") (pin "1") (pinfunction "1_1") (pintype "unspecified"))
      (node (ref "C23") (pin "1") (pinfunction "1_1") (pintype "unspecified"))
      (node (ref "C24") (pin "1") (pinfunction "1_1") (pintype "unspecified"))
      (node (ref "C25") (pin "1") (pinfunction "1_1") (pintype "unspecified"))
      (node (ref "C26") (pin "2") (pinfunction "2_2") (pintype "unspecified"))
      (node (ref "C27") (pin "2") (pinfunction "2_2") (pintype "unspecified"))
      (node (ref "C28") (pin "2") (pinfunction "2_2") (pintype "unspecified"))
      (node (ref "C29") (pin "2") (pinfunction "2_2") (pintype "unspecified"))
      (node (ref "C30") (pin "1") (pinfunction "1_1") (pintype "unspecified"))
      (node (ref "C31") (pin "1") (pinfunction "1_1") (pintype "unspecified"))
      (node (ref "C32") (pin "1") (pinfunction "1_1") (pintype "unspecified"))
      (node (ref "C33") (pin "1") (pinfunction "1_1") (pintype "unspecified"))
      (node (ref "C34") (pin "1") (pinfunction "1_1") (pintype "unspecified"))
      (node (ref "C35") (pin "1") (pinfunction "1_1") (pintype "unspecified"))
      (node (ref "C36") (pin "1") (pinfunction "1_1") (pintype "unspecified"))
      (node (ref "C37") (pin "1") (pinfunction "1_1") (pintype "unspecified"))
      (node (ref "C38") (pin "1") (pinfunction "1_1") (pintype "unspecified"))
      (node (ref "C39") (pin "1") (pinfunction "1_1") (pintype "unspecified"))
      (node (ref "C4") (pin "2") (pinfunction "2_2") (pintype "unspecified"))
      (node (ref "C40") (pin "1") (pinfunction "1_1") (pintype "unspecified"))
      (node (ref "C41") (pin "1") (pinfunction "1_1") (pintype "unspecified"))
      (node (ref "C42") (pin "1") (pinfunction "1_1") (pintype "unspecified"))
      (node (ref "C43") (pin "2") (pinfunction "2_2") (pintype "unspecified"))
      (node (ref "C48") (pin "2") (pinfunction "2_2") (pintype "unspecified"))
      (node (ref "C49") (pin "2") (pinfunction "2_2") (pintype "unspecified"))
      (node (ref "J1") (pin "10") (pinfunction "10_10") (pintype "unspecified"))
      (node (ref "J1") (pin "2") (pinfunction "2_2") (pintype "unspecified"))
      (node (ref "J2") (pin "19") (pinfunction "19_19") (pintype "unspecified"))
      (node (ref "J2") (pin "21") (pinfunction "21_21") (pintype "unspecified"))
      (node (ref "J2") (pin "3") (pinfunction "3_3") (pintype "unspecified"))
      (node (ref "J2") (pin "30") (pinfunction "30_30") (pintype "unspecified"))
      (node (ref "J2") (pin "39") (pinfunction "39_39") (pintype "unspecified"))
      (node (ref "J2") (pin "40") (pinfunction "40_40") (pintype "unspecified"))
      (node (ref "J2") (pin "5") (pinfunction "5_5") (pintype "unspecified"))
      (node (ref "J2") (pin "51") (pinfunction "51_51") (pintype "unspecified"))
      (node (ref "J2") (pin "52") (pinfunction "52_52") (pintype "unspecified"))
      (node (ref "J2") (pin "60") (pinfunction "60_60") (pintype "unspecified"))
      (node (ref "J2") (pin "61") (pinfunction "61_61") (pintype "unspecified"))
      (node (ref "J2") (pin "62") (pinfunction "62_62") (pintype "unspecified"))
      (node (ref "J2") (pin "63") (pinfunction "63_63") (pintype "unspecified"))
      (node (ref "J2") (pin "64") (pinfunction "64_64") (pintype "unspecified"))
      (node (ref "J2") (pin "65") (pinfunction "65_65") (pintype "unspecified"))
      (node (ref "J2") (pin "69") (pinfunction "69_69") (pintype "unspecified"))
      (node (ref "J2") (pin "7") (pinfunction "7_7") (pintype "unspecified"))
      (node (ref "J2") (pin "70") (pinfunction "70_70") (pintype "unspecified"))
      (node (ref "J2") (pin "9") (pinfunction "9_9") (pintype "unspecified"))
      (node (ref "P1") (pin "10") (pinfunction "10_10") (pintype "unspecified"))
      (node (ref "P1") (pin "2") (pinfunction "2_2") (pintype "unspecified"))
      (node (ref "Q1") (pin "3") (pinfunction "E_3") (pintype "unspecified"))
      (node (ref "R1") (pin "2") (pinfunction "2_2") (pintype "unspecified"))
      (node (ref "R15") (pin "1") (pinfunction "1_1") (pintype "unspecified"))
      (node (ref "RP1") (pin "7") (pinfunction "7_7") (pintype "unspecified"))
      (node (ref "RP2") (pin "4") (pinfunction "4_4") (pintype "unspecified"))
      (node (ref "U1") (pin "105") (pinfunction "GND_105") (pintype "unspecified"))
      (node (ref "U1") (pin "106") (pinfunction "GND_PLL2_106") (pintype "unspecified"))
      (node (ref "U1") (pin "108") (pinfunction "GND_PLL2_108") (pintype "unspecified"))
      (node (ref "U1") (pin "110") (pinfunction "GNDA_PLL2_110") (pintype "unspecified"))
      (node (ref "U1") (pin "111") (pinfunction "GND_111") (pintype "unspecified"))
      (node (ref "U1") (pin "117") (pinfunction "GND_117") (pintype "unspecified"))
      (node (ref "U1") (pin "123") (pinfunction "GND_123") (pintype "unspecified"))
      (node (ref "U1") (pin "128") (pinfunction "GND_128") (pintype "unspecified"))
      (node (ref "U1") (pin "130") (pinfunction "GND_130") (pintype "unspecified"))
      (node (ref "U1") (pin "140") (pinfunction "GND_140") (pintype "unspecified"))
      (node (ref "U1") (pin "17") (pinfunction "CLK0,_LVDSCLK0p_INPUT_17") (pintype "input"))
      (node (ref "U1") (pin "19") (pinfunction "GND_19") (pintype "unspecified"))
      (node (ref "U1") (pin "21") (pinfunction "CLK2,_LVDSCLK1p_INPUT_21") (pintype "input"))
      (node (ref "U1") (pin "22") (pinfunction "CLK3,_LVDSCLK1n_INPUT_22") (pintype "input"))
      (node (ref "U1") (pin "27") (pinfunction "GND_27") (pintype "unspecified"))
      (node (ref "U1") (pin "33") (pinfunction "GND_33") (pintype "unspecified"))
      (node (ref "U1") (pin "34") (pinfunction "GND_PLL1_34") (pintype "unspecified"))
      (node (ref "U1") (pin "36") (pinfunction "GND_PLL1_36") (pintype "unspecified"))
      (node (ref "U1") (pin "38") (pinfunction "GNDA_PLL1_38") (pintype "unspecified"))
      (node (ref "U1") (pin "39") (pinfunction "GND_39") (pintype "unspecified"))
      (node (ref "U1") (pin "49") (pinfunction "GND_49") (pintype "unspecified"))
      (node (ref "U1") (pin "56") (pinfunction "GND_56") (pintype "unspecified"))
      (node (ref "U1") (pin "6") (pinfunction "GND_6") (pintype "unspecified"))
      (node (ref "U1") (pin "61") (pinfunction "GND_61") (pintype "unspecified"))
      (node (ref "U1") (pin "68") (pinfunction "GND_68") (pintype "unspecified"))
      (node (ref "U1") (pin "78") (pinfunction "GND_78") (pintype "unspecified"))
      (node (ref "U1") (pin "80") (pinfunction "GND_80") (pintype "unspecified"))
      (node (ref "U1") (pin "85") (pinfunction "MSEL0_85") (pintype "input"))
      (node (ref "U1") (pin "88") (pinfunction "CLK7,_LVDSCLK3n_INPUT_88") (pintype "input"))
      (node (ref "U1") (pin "89") (pinfunction "CLK6,_LVDSCLK3p_INPUT_89") (pintype "input"))
      (node (ref "U1") (pin "90") (pinfunction "CLK5,_LVDSCLK2n_INPUT_90") (pintype "input"))
      (node (ref "U1") (pin "91") (pinfunction "CLK4,_LVDSCLK2p_INPUT_91") (pintype "input"))
      (node (ref "U1") (pin "98") (pinfunction "GND_98") (pintype "unspecified"))
      (node (ref "U10") (pin "3") (pinfunction "GND_3") (pintype "unspecified"))
      (node (ref "U11") (pin "1") (pinfunction "SYNC_1") (pintype "unspecified"))
      (node (ref "U11") (pin "3") (pinfunction "GND_3") (pintype "unspecified"))
      (node (ref "U11") (pin "6") (pinfunction "-Sense_6") (pintype "unspecified"))
      (node (ref "U12") (pin "4") (pinfunction "GND_4") (pintype "unspecified"))
      (node (ref "U17") (pin "4") (pinfunction "GND_4") (pintype "unspecified"))
      (node (ref "U18") (pin "4") (pinfunction "GND_4") (pintype "unspecified"))
      (node (ref "U19") (pin "2") (pinfunction "Vi-_2") (pintype "unspecified"))
      (node (ref "U3") (pin "2") (pinfunction "NC_2") (pintype "unspecified"))
      (node (ref "U4") (pin "10") (pinfunction "GND_10") (pintype "unspecified"))
      (node (ref "U5") (pin "4") (pinfunction "VSS_4") (pintype "unspecified"))
      (node (ref "U5") (pin "5") (pinfunction "DGND_5") (pintype "unspecified"))
      (node (ref "U6") (pin "2") (pinfunction "K1_2") (pintype "unspecified"))
      (node (ref "U6") (pin "3") (pinfunction "K2_3") (pintype "unspecified"))
      (node (ref "U7") (pin "2") (pinfunction "K1_2") (pintype "unspecified"))
      (node (ref "U7") (pin "3") (pinfunction "K2_3") (pintype "unspecified"))
      (node (ref "U8") (pin "2") (pinfunction "K1_2") (pintype "unspecified"))
      (node (ref "U8") (pin "3") (pinfunction "K2_3") (pintype "unspecified"))
    )
    (net (code "25") (name "DO.DR+") (class "Default")
      (node (ref "J2") (pin "8") (pinfunction "8_8") (pintype "unspecified"))
      (node (ref "R21") (pin "2") (pinfunction "2_2") (pintype "unspecified"))
      (node (ref "R22") (pin "2") (pinfunction "2_2") (pintype "unspecified"))
      (node (ref "R24") (pin "2") (pinfunction "2_2") (pintype "unspecified"))
      (node (ref "R25") (pin "2") (pinfunction "2_2") (pintype "unspecified"))
    )
    (net (code "26") (name "DO.DR-") (class "Default")
      (node (ref "J2") (pin "6") (pinfunction "6_6") (pintype "unspecified"))
      (node (ref "Q1") (pin "2") (pinfunction "C_2") (pintype "unspecified"))
    )
    (net (code "27") (name "DRAM_A0") (class "Default")
      (node (ref "U1") (pin "52") (pinfunction "IO,_LVDS70p,_DQ1B4_52") (pintype "bidirectional"))
    )
    (net (code "28") (name "DRAM_A1") (class "Default")
      (node (ref "U1") (pin "53") (pinfunction "IO,_LVDS68p,_DQ1B3_53") (pintype "bidirectional"))
    )
    (net (code "29") (name "DRAM_A2") (class "Default")
      (node (ref "U1") (pin "51") (pinfunction "IO,_VREFB4N1_51") (pintype "bidirectional"))
    )
    (net (code "30") (name "DRAM_A3") (class "Default")
      (node (ref "U1") (pin "55") (pinfunction "IO,_LVDS68n,_DQ1B2_55") (pintype "bidirectional"))
    )
    (net (code "31") (name "DRAM_A4") (class "Default")
      (node (ref "U1") (pin "58") (pinfunction "IO,_LVDS67n,_DQ1B0_58") (pintype "bidirectional"))
    )
    (net (code "32") (name "DRAM_A5") (class "Default")
      (node (ref "U1") (pin "60") (pinfunction "IO,_LVDS66n_60") (pintype "bidirectional"))
    )
    (net (code "33") (name "DRAM_A6") (class "Default")
      (node (ref "U1") (pin "57") (pinfunction "IO,_LVDS67p,_DQ1B1_57") (pintype "bidirectional"))
    )
    (net (code "34") (name "DRAM_A7") (class "Default")
      (node (ref "U1") (pin "64") (pinfunction "IO,_LVDS60p,_(DPCLK4/DQS0B)_64") (pintype "bidirectional"))
    )
    (net (code "35") (name "DRAM_A8") (class "Default")
      (node (ref "U1") (pin "59") (pinfunction "IO,_LVDS66p_59") (pintype "bidirectional"))
    )
    (net (code "36") (name "DRAM_A9") (class "Default")
      (node (ref "U1") (pin "67") (pinfunction "IO,_LVDS59n_67") (pintype "bidirectional"))
    )
    (net (code "37") (name "DRAM_A10") (class "Default")
      (node (ref "U1") (pin "47") (pinfunction "IO,_LVDS74p,_(DPCLK2/DQS1B)_47") (pintype "bidirectional"))
    )
    (net (code "38") (name "DRAM_A11") (class "Default")
      (node (ref "U1") (pin "63") (pinfunction "IO,_VREFB4N0_63") (pintype "bidirectional"))
    )
    (net (code "39") (name "DRAM_A12") (class "Default")
      (node (ref "U1") (pin "65") (pinfunction "IO,_LVDS60n_65") (pintype "bidirectional"))
    )
    (net (code "40") (name "DRAM_BA0") (class "Default")
      (node (ref "U1") (pin "44") (pinfunction "IO,_LVDS75p,_DQ1B6_44") (pintype "bidirectional"))
    )
    (net (code "41") (name "DRAM_BA1") (class "Default")
      (node (ref "U1") (pin "48") (pinfunction "IO,_LVDS74n_48") (pintype "bidirectional"))
    )
    (net (code "42") (name "DRAM_CKE") (class "Default")
      (node (ref "U1") (pin "32") (pinfunction "IO,_PLL1_OUTn_32") (pintype "bidirectional"))
    )
    (net (code "43") (name "DRAM_CLK") (class "Default")
      (node (ref "U1") (pin "31") (pinfunction "IO,_PLL1_OUTp_31") (pintype "bidirectional"))
    )
    (net (code "44") (name "DRAM_D0") (class "Default")
      (node (ref "U1") (pin "134") (pinfunction "IO,_LVDS23p,_DQ1T4_134") (pintype "bidirectional"))
    )
    (net (code "45") (name "DRAM_D1") (class "Default")
      (node (ref "U1") (pin "135") (pinfunction "IO,_LVDS19n,_DQ1T5_135") (pintype "bidirectional"))
    )
    (net (code "46") (name "DRAM_D2") (class "Default")
      (node (ref "U1") (pin "141") (pinfunction "IO,_LVDS17p,_DQ1T8_141") (pintype "bidirectional"))
    )
    (net (code "47") (name "DRAM_D3") (class "Default")
      (node (ref "U1") (pin "142") (pinfunction "IO,_LVDS17n_(DEV_CLRn)_142") (pintype "bidirectional"))
    )
    (net (code "48") (name "DRAM_D4") (class "Default")
      (node (ref "U1") (pin "143") (pinfunction "IO,_LVDS16p,_(DM1T/BWS#1T)_143") (pintype "bidirectional"))
    )
    (net (code "49") (name "DRAM_D5") (class "Default")
      (node (ref "U1") (pin "144") (pinfunction "IO,_LVDS16n_144") (pintype "bidirectional"))
    )
    (net (code "50") (name "DRAM_D6") (class "Default")
      (node (ref "U1") (pin "3") (pinfunction "IO,_LVDS15p_(CRC_ERROR)_3") (pintype "bidirectional"))
    )
    (net (code "51") (name "DRAM_D7") (class "Default")
      (node (ref "U1") (pin "4") (pinfunction "IO,_LVDS15n_(CLKUSR)_4") (pintype "bidirectional"))
    )
    (net (code "52") (name "DRAM_D8") (class "Default")
      (node (ref "U1") (pin "136") (pinfunction "IO,_LVDS19p,_(DPCLK10/DQS1T)_136") (pintype "bidirectional"))
    )
    (net (code "53") (name "DRAM_D9") (class "Default")
      (node (ref "U1") (pin "139") (pinfunction "IO,_LVDS18p,_DQ1T7_139") (pintype "bidirectional"))
    )
    (net (code "54") (name "DRAM_D10") (class "Default")
      (node (ref "U1") (pin "137") (pinfunction "IO,_LVDS18n,_DQ1T6_137") (pintype "bidirectional"))
    )
    (net (code "55") (name "DRAM_D11") (class "Default")
      (node (ref "U1") (pin "133") (pinfunction "IO,_LVDS23n,_DQ1T3_133") (pintype "bidirectional"))
    )
    (net (code "56") (name "DRAM_D12") (class "Default")
      (node (ref "U1") (pin "132") (pinfunction "IO,_VREFB2N1_132") (pintype "bidirectional"))
    )
    (net (code "57") (name "DRAM_D13") (class "Default")
      (node (ref "U1") (pin "125") (pinfunction "IO,_LVDS29n,_DQ1T0_125") (pintype "bidirectional"))
    )
    (net (code "58") (name "DRAM_D14") (class "Default")
      (node (ref "U1") (pin "129") (pinfunction "IO,_LVDS26p,_DQ1T2_129") (pintype "bidirectional"))
    )
    (net (code "59") (name "DRAM_D15") (class "Default")
      (node (ref "U1") (pin "126") (pinfunction "IO,_LVDS29p,_DQ1T1_126") (pintype "bidirectional"))
    )
    (net (code "60") (name "DRAM_LDQM") (class "Default")
      (node (ref "U1") (pin "41") (pinfunction "IO,_LVDS77p,_(DM1B/BWS#1B)_41") (pintype "bidirectional"))
    )
    (net (code "61") (name "DRAM_NCAS") (class "Default")
      (node (ref "U1") (pin "43") (pinfunction "IO,_LVDS76n,_DQ1B7_43") (pintype "bidirectional"))
    )
    (net (code "62") (name "DRAM_NCS") (class "Default")
      (node (ref "U1") (pin "45") (pinfunction "IO,_LVDS75n,_DQ1B5_45") (pintype "bidirectional"))
    )
    (net (code "63") (name "DRAM_NRAS") (class "Default")
      (node (ref "U1") (pin "42") (pinfunction "IO,_LVDS76p,_DQ1B8_42") (pintype "bidirectional"))
    )
    (net (code "64") (name "DRAM_NWE") (class "Default")
      (node (ref "U1") (pin "40") (pinfunction "IO,_LVDS77n_(DEV_OE)_40") (pintype "bidirectional"))
    )
    (net (code "65") (name "DRAM_UDQM") (class "Default")
      (node (ref "U1") (pin "7") (pinfunction "IO,_VREFB1N0_7") (pintype "bidirectional"))
    )
    (net (code "66") (name "DVS+3V3") (class "Default")
      (node (ref "C1") (pin "2") (pinfunction "2_2") (pintype "unspecified"))
      (node (ref "C28") (pin "1") (pinfunction "1_1") (pintype "unspecified"))
      (node (ref "C29") (pin "1") (pinfunction "1_1") (pintype "unspecified"))
      (node (ref "C30") (pin "2") (pinfunction "2_2") (pintype "unspecified"))
      (node (ref "C31") (pin "2") (pinfunction "2_2") (pintype "unspecified"))
      (node (ref "C32") (pin "2") (pinfunction "2_2") (pintype "unspecified"))
      (node (ref "C33") (pin "2") (pinfunction "2_2") (pintype "unspecified"))
      (node (ref "C34") (pin "2") (pinfunction "2_2") (pintype "unspecified"))
      (node (ref "C35") (pin "2") (pinfunction "2_2") (pintype "unspecified"))
      (node (ref "C36") (pin "2") (pinfunction "2_2") (pintype "unspecified"))
      (node (ref "C37") (pin "2") (pinfunction "2_2") (pintype "unspecified"))
      (node (ref "C38") (pin "2") (pinfunction "2_2") (pintype "unspecified"))
      (node (ref "C39") (pin "2") (pinfunction "2_2") (pintype "unspecified"))
      (node (ref "C40") (pin "2") (pinfunction "2_2") (pintype "unspecified"))
      (node (ref "C41") (pin "2") (pinfunction "2_2") (pintype "unspecified"))
      (node (ref "C42") (pin "2") (pinfunction "2_2") (pintype "unspecified"))
      (node (ref "C43") (pin "1") (pinfunction "1_1") (pintype "unspecified"))
      (node (ref "C48") (pin "1") (pinfunction "1_1") (pintype "unspecified"))
      (node (ref "C49") (pin "1") (pinfunction "1_1") (pintype "unspecified"))
      (node (ref "J1") (pin "4") (pinfunction "4_4") (pintype "unspecified"))
      (node (ref "P1") (pin "4") (pinfunction "4_4") (pintype "unspecified"))
      (node (ref "P1") (pin "6") (pinfunction "6_6") (pintype "unspecified"))
      (node (ref "R11") (pin "1") (pinfunction "1_1") (pintype "unspecified"))
      (node (ref "R13") (pin "1") (pinfunction "1_1") (pintype "unspecified"))
      (node (ref "R2") (pin "2") (pinfunction "2_2") (pintype "unspecified"))
      (node (ref "RP1") (pin "5") (pinfunction "5_5") (pintype "unspecified"))
      (node (ref "RP1") (pin "6") (pinfunction "6_6") (pintype "unspecified"))
      (node (ref "RP1") (pin "8") (pinfunction "8_8") (pintype "unspecified"))
      (node (ref "RP2") (pin "1") (pinfunction "1_1") (pintype "unspecified"))
      (node (ref "RP2") (pin "3") (pinfunction "3_3") (pintype "unspecified"))
      (node (ref "U1") (pin "102") (pinfunction "VCCIO3_102") (pintype "unspecified"))
      (node (ref "U1") (pin "116") (pinfunction "VCCIO2_116") (pintype "unspecified"))
      (node (ref "U1") (pin "127") (pinfunction "VCCIO2_127") (pintype "unspecified"))
      (node (ref "U1") (pin "138") (pinfunction "VCCIO2_138") (pintype "unspecified"))
      (node (ref "U1") (pin "23") (pinfunction "VCCIO1_23") (pintype "unspecified"))
      (node (ref "U1") (pin "29") (pinfunction "VCCIO1_29") (pintype "unspecified"))
      (node (ref "U1") (pin "46") (pinfunction "VCCIO4_46") (pintype "unspecified"))
      (node (ref "U1") (pin "5") (pinfunction "VCCIO1_5") (pintype "unspecified"))
      (node (ref "U1") (pin "54") (pinfunction "VCCIO4_54") (pintype "unspecified"))
      (node (ref "U1") (pin "66") (pinfunction "VCCIO4_66") (pintype "unspecified"))
      (node (ref "U1") (pin "77") (pinfunction "VCCIO3_77") (pintype "unspecified"))
      (node (ref "U1") (pin "95") (pinfunction "VCCIO3_95") (pintype "unspecified"))
      (node (ref "U10") (pin "1") (pinfunction "EN_1") (pintype "unspecified"))
      (node (ref "U10") (pin "2") (pinfunction "IN_2") (pintype "unspecified"))
      (node (ref "U11") (pin "4") (pinfunction "Vo_4") (pintype "unspecified"))
      (node (ref "U11") (pin "5") (pinfunction "+Sense_5") (pintype "unspecified"))
      (node (ref "U12") (pin "1") (pinfunction "VCC_1") (pintype "unspecified"))
      (node (ref "U17") (pin "1") (pinfunction "VCC_1") (pintype "unspecified"))
      (node (ref "U18") (pin "1") (pinfunction "VCC_1") (pintype "unspecified"))
      (node (ref "U3") (pin "4") (pintype "unspecified"))
      (node (ref "U4") (pin "1") (pinfunction "VCC_1") (pintype "unspecified"))
      (node (ref "U4") (pin "2") (pinfunction "VCC_2") (pintype "unspecified"))
      (node (ref "U4") (pin "9") (pinfunction "VCC_9") (pintype "unspecified"))
    )
    (net (code "67") (name "D_DRIVER") (class "Default")
      (node (ref "R23") (pin "2") (pinfunction "2_2") (pintype "unspecified"))
      (node (ref "U1") (pin "114") (pinfunction "IO,_LVDS36n_114") (pintype "bidirectional"))
    )
    (net (code "68") (name "ISOVS+") (class "Default")
      (node (ref "C2") (pin "1") (pinfunction "1_1") (pintype "unspecified"))
      (node (ref "C3") (pin "1") (pinfunction "1_1") (pintype "unspecified"))
      (node (ref "C5") (pin "1") (pinfunction "1_1") (pintype "unspecified"))
      (node (ref "C6") (pin "1") (pinfunction "1_1") (pintype "unspecified"))
      (node (ref "C7") (pin "1") (pinfunction "1_1") (pintype "unspecified"))
      (node (ref "R3") (pin "1") (pinfunction "1_1") (pintype "unspecified"))
      (node (ref "R4") (pin "1") (pinfunction "1_1") (pintype "unspecified"))
      (node (ref "R5") (pin "1") (pinfunction "1_1") (pintype "unspecified"))
      (node (ref "R6") (pin "1") (pinfunction "1_1") (pintype "unspecified"))
      (node (ref "R7") (pin "1") (pinfunction "1_1") (pintype "unspecified"))
      (node (ref "R8") (pin "1") (pinfunction "1_1") (pintype "unspecified"))
      (node (ref "U19") (pin "6") (pinfunction "Vo+_6") (pintype "unspecified"))
      (node (ref "U6") (pin "8") (pinfunction "VCC_8") (pintype "unspecified"))
      (node (ref "U7") (pin "8") (pinfunction "VCC_8") (pintype "unspecified"))
      (node (ref "U8") (pin "8") (pinfunction "VCC_8") (pintype "unspecified"))
    )
    (net (code "69") (name "ISOVS-") (class "Default")
      (node (ref "C2") (pin "2") (pinfunction "2_2") (pintype "unspecified"))
      (node (ref "C3") (pin "2") (pinfunction "2_2") (pintype "unspecified"))
      (node (ref "C5") (pin "2") (pinfunction "2_2") (pintype "unspecified"))
      (node (ref "C6") (pin "2") (pinfunction "2_2") (pintype "unspecified"))
      (node (ref "C7") (pin "2") (pinfunction "2_2") (pintype "unspecified"))
      (node (ref "U19") (pin "4") (pinfunction "Vo-_4") (pintype "unspecified"))
      (node (ref "U6") (pin "5") (pinfunction "GND_5") (pintype "unspecified"))
      (node (ref "U7") (pin "5") (pinfunction "GND_5") (pintype "unspecified"))
      (node (ref "U8") (pin "5") (pinfunction "GND_5") (pintype "unspecified"))
    )
    (net (code "70") (name "LASER_CTRL1") (class "Default")
      (node (ref "RN1") (pin "3") (pinfunction "3_3") (pintype "unspecified"))
      (node (ref "U1") (pin "79") (pinfunction "IO,_VREFB3N1_79") (pintype "bidirectional"))
    )
    (net (code "71") (name "LASER_CTRL2") (class "Default")
      (node (ref "RN1") (pin "4") (pinfunction "4_4") (pintype "unspecified"))
      (node (ref "U1") (pin "75") (pinfunction "IO,_LVDS54n_(INIT_DONE)_75") (pintype "bidirectional"))
    )
    (net (code "72") (name "LASER_CTRL3") (class "Default")
      (node (ref "RN1") (pin "1") (pinfunction "1_1") (pintype "unspecified"))
      (node (ref "U1") (pin "76") (pinfunction "IO,_LVDS54p_(nCEO)_76") (pintype "bidirectional"))
    )
    (net (code "73") (name "LASER_CTRL4") (class "Default")
      (node (ref "RN1") (pin "2") (pinfunction "2_2") (pintype "unspecified"))
      (node (ref "U1") (pin "74") (pinfunction "IO,_LVDS56p,_DQ1R8_74") (pintype "bidirectional"))
    )
    (net (code "74") (name "LASER_CTRL5") (class "Default")
      (node (ref "R9") (pin "1") (pinfunction "1_1") (pintype "unspecified"))
      (node (ref "U1") (pin "87") (pinfunction "IO,_LVDS48p,_(DPCLK6/DQS1R)_87") (pintype "bidirectional"))
    )
    (net (code "75") (name "LASER_CTRL6") (class "Default")
      (node (ref "R10") (pin "1") (pinfunction "1_1") (pintype "unspecified"))
      (node (ref "U1") (pin "73") (pinfunction "IO,_LVDS56n,_(DM1R/BWS#1R)_73") (pintype "bidirectional"))
    )
    (net (code "76") (name "LASER_P1") (class "Default")
      (node (ref "J2") (pin "34") (pinfunction "34_34") (pintype "unspecified"))
      (node (ref "R3") (pin "2") (pinfunction "2_2") (pintype "unspecified"))
      (node (ref "U6") (pin "7") (pinfunction "OUT1_7") (pintype "unspecified"))
    )
    (net (code "77") (name "LASER_P2") (class "Default")
      (node (ref "J2") (pin "33") (pinfunction "33_33") (pintype "unspecified"))
      (node (ref "R4") (pin "2") (pinfunction "2_2") (pintype "unspecified"))
      (node (ref "U6") (pin "6") (pinfunction "OUT2_6") (pintype "unspecified"))
    )
    (net (code "78") (name "LASER_P3") (class "Default")
      (node (ref "J2") (pin "32") (pinfunction "32_32") (pintype "unspecified"))
      (node (ref "R5") (pin "2") (pinfunction "2_2") (pintype "unspecified"))
      (node (ref "U7") (pin "7") (pinfunction "OUT1_7") (pintype "unspecified"))
    )
    (net (code "79") (name "LASER_P4") (class "Default")
      (node (ref "J2") (pin "31") (pinfunction "31_31") (pintype "unspecified"))
      (node (ref "R6") (pin "2") (pinfunction "2_2") (pintype "unspecified"))
      (node (ref "U7") (pin "6") (pinfunction "OUT2_6") (pintype "unspecified"))
    )
    (net (code "80") (name "LASER_P5") (class "Default")
      (node (ref "J2") (pin "18") (pinfunction "18_18") (pintype "unspecified"))
      (node (ref "R7") (pin "2") (pinfunction "2_2") (pintype "unspecified"))
      (node (ref "U8") (pin "7") (pinfunction "OUT1_7") (pintype "unspecified"))
    )
    (net (code "81") (name "LASER_P6") (class "Default")
      (node (ref "J2") (pin "20") (pinfunction "20_20") (pintype "unspecified"))
      (node (ref "R8") (pin "2") (pinfunction "2_2") (pintype "unspecified"))
      (node (ref "U8") (pin "6") (pinfunction "OUT2_6") (pintype "unspecified"))
    )
    (net (code "82") (name "LDAC") (class "Default")
      (node (ref "U1") (pin "112") (pinfunction "IO,_LVDS37n_112") (pintype "bidirectional"))
      (node (ref "U5") (pin "7") (pinfunction "~LDAC~_7") (pintype "unspecified"))
    )
    (net (code "83") (name "NCE") (class "Default")
      (node (ref "J1") (pin "6") (pinfunction "6_6") (pintype "unspecified"))
      (node (ref "RP1") (pin "2") (pinfunction "2_2") (pintype "unspecified"))
      (node (ref "U1") (pin "16") (pinfunction "nCE_16") (pintype "input"))
    )
    (net (code "84") (name "NCONFIG") (class "Default")
      (node (ref "J1") (pin "5") (pinfunction "5_5") (pintype "unspecified"))
      (node (ref "RP1") (pin "1") (pinfunction "1_1") (pintype "unspecified"))
      (node (ref "U1") (pin "20") (pinfunction "nCONFIG_20") (pintype "input"))
    )
    (net (code "85") (name "NCSO") (class "Default")
      (node (ref "J1") (pin "8") (pinfunction "8_8") (pintype "unspecified"))
      (node (ref "U1") (pin "2") (pinfunction "IO,_(nCSO)_2") (pintype "bidirectional"))
      (node (ref "U4") (pin "7") (pinfunction "nCS_7") (pintype "unspecified"))
    )
    (net (code "86") (name "NSTATUS") (class "Default")
      (node (ref "RP1") (pin "4") (pinfunction "4_4") (pintype "unspecified"))
      (node (ref "U1") (pin "82") (pinfunction "nSTATUS_82") (pintype "bidirectional"))
    )
    (net (code "87") (name "Net-(Q1-B)") (class "Default")
      (node (ref "Q1") (pin "1") (pinfunction "B_1") (pintype "unspecified"))
      (node (ref "R23") (pin "1") (pinfunction "1_1") (pintype "unspecified"))
    )
    (net (code "88") (name "Net-(U1F-MSEL1)") (class "Default")
      (node (ref "R1") (pin "1") (pinfunction "1_1") (pintype "unspecified"))
      (node (ref "R2") (pin "1") (pinfunction "1_1") (pintype "unspecified"))
      (node (ref "U1") (pin "84") (pinfunction "MSEL1_84") (pintype "input"))
    )
    (net (code "89") (name "Net-(U5-VOUTC)") (class "Default")
      (node (ref "TP1") (pin "1") (pinfunction "1_1") (pintype "unspecified"))
      (node (ref "U5") (pin "27") (pinfunction "VOUTC_27") (pintype "unspecified"))
    )
    (net (code "90") (name "Net-(U5-VOUTD)") (class "Default")
      (node (ref "TP2") (pin "1") (pinfunction "1_1") (pintype "unspecified"))
      (node (ref "U5") (pin "26") (pinfunction "VOUTD_26") (pintype "unspecified"))
    )
    (net (code "91") (name "Net-(U6-A1)") (class "Default")
      (node (ref "RN1") (pin "6") (pinfunction "6_6") (pintype "unspecified"))
      (node (ref "U6") (pin "1") (pinfunction "A1_1") (pintype "unspecified"))
    )
    (net (code "92") (name "Net-(U6-A2)") (class "Default")
      (node (ref "RN1") (pin "5") (pinfunction "5_5") (pintype "unspecified"))
      (node (ref "U6") (pin "4") (pinfunction "A2_4") (pintype "unspecified"))
    )
    (net (code "93") (name "Net-(U7-A1)") (class "Default")
      (node (ref "RN1") (pin "8") (pinfunction "8_8") (pintype "unspecified"))
      (node (ref "U7") (pin "1") (pinfunction "A1_1") (pintype "unspecified"))
    )
    (net (code "94") (name "Net-(U7-A2)") (class "Default")
      (node (ref "RN1") (pin "7") (pinfunction "7_7") (pintype "unspecified"))
      (node (ref "U7") (pin "4") (pinfunction "A2_4") (pintype "unspecified"))
    )
    (net (code "95") (name "Net-(U8-A1)") (class "Default")
      (node (ref "R9") (pin "2") (pinfunction "2_2") (pintype "unspecified"))
      (node (ref "U8") (pin "1") (pinfunction "A1_1") (pintype "unspecified"))
    )
    (net (code "96") (name "Net-(U8-A2)") (class "Default")
      (node (ref "R10") (pin "2") (pinfunction "2_2") (pintype "unspecified"))
      (node (ref "U8") (pin "4") (pinfunction "A2_4") (pintype "unspecified"))
    )
    (net (code "97") (name "Net-(U10-EF)") (class "Default")
      (node (ref "R11") (pin "2") (pinfunction "2_2") (pintype "unspecified"))
      (node (ref "U10") (pin "5") (pinfunction "EF_5") (pintype "unspecified"))
    )
    (net (code "98") (name "Net-(U11-INH{slash}UVLO)") (class "Default")
      (node (ref "R14") (pin "1") (pinfunction "1_1") (pintype "unspecified"))
      (node (ref "U11") (pin "10") (pinfunction "INH/UVLO_10") (pintype "unspecified"))
    )
    (net (code "99") (name "Net-(U11-TT)") (class "Default")
      (node (ref "R13") (pin "2") (pinfunction "2_2") (pintype "unspecified"))
      (node (ref "U11") (pin "8") (pinfunction "TT_8") (pintype "unspecified"))
    )
    (net (code "100") (name "Net-(U11-Track)") (class "Default")
      (node (ref "R12") (pin "1") (pinfunction "1_1") (pintype "unspecified"))
      (node (ref "U11") (pin "9") (pinfunction "Track_9") (pintype "unspecified"))
    )
    (net (code "101") (name "Net-(U11-VoAdj)") (class "Default")
      (node (ref "R15") (pin "2") (pinfunction "2_2") (pintype "unspecified"))
      (node (ref "U11") (pin "7") (pinfunction "VoAdj_7") (pintype "unspecified"))
    )
    (net (code "102") (name "RESET") (class "Default")
      (node (ref "U1") (pin "30") (pinfunction "IO_30") (pintype "bidirectional"))
      (node (ref "U5") (pin "6") (pinfunction "~RESET~_6") (pintype "unspecified"))
    )
    (net (code "103") (name "RS422_R1+") (class "Default")
      (node (ref "J2") (pin "22") (pinfunction "22_22") (pintype "unspecified"))
      (node (ref "R16") (pin "2") (pinfunction "2_2") (pintype "unspecified"))
      (node (ref "U12") (pin "8") (pinfunction "A_8") (pintype "input"))
    )
    (net (code "104") (name "RS422_R1-") (class "Default")
      (node (ref "J2") (pin "23") (pinfunction "23_23") (pintype "unspecified"))
      (node (ref "R16") (pin "1") (pinfunction "1_1") (pintype "unspecified"))
      (node (ref "U12") (pin "7") (pinfunction "B_7") (pintype "input"))
    )
    (net (code "105") (name "RS422_R4+") (class "Default")
      (node (ref "J2") (pin "24") (pinfunction "24_24") (pintype "unspecified"))
      (node (ref "R26") (pin "2") (pinfunction "2_2") (pintype "unspecified"))
      (node (ref "U17") (pin "8") (pinfunction "A_8") (pintype "input"))
    )
    (net (code "106") (name "RS422_R4-") (class "Default")
      (node (ref "J2") (pin "25") (pinfunction "25_25") (pintype "unspecified"))
      (node (ref "R26") (pin "1") (pinfunction "1_1") (pintype "unspecified"))
      (node (ref "U17") (pin "7") (pinfunction "B_7") (pintype "input"))
    )
    (net (code "107") (name "RS422_R5+") (class "Default")
      (node (ref "R27") (pin "2") (pinfunction "2_2") (pintype "unspecified"))
      (node (ref "U18") (pin "8") (pinfunction "A_8") (pintype "input"))
    )
    (net (code "108") (name "RS422_R5-") (class "Default")
      (node (ref "R27") (pin "1") (pinfunction "1_1") (pintype "unspecified"))
      (node (ref "U18") (pin "7") (pinfunction "B_7") (pintype "input"))
    )
    (net (code "109") (name "RS422_T1+") (class "Default")
      (node (ref "J2") (pin "28") (pinfunction "28_28") (pintype "unspecified"))
      (node (ref "U12") (pin "5") (pinfunction "Y_5") (pintype "output"))
    )
    (net (code "110") (name "RS422_T1-") (class "Default")
      (node (ref "J2") (pin "29") (pinfunction "29_29") (pintype "unspecified"))
      (node (ref "U12") (pin "6") (pinfunction "Z_6") (pintype "output"))
    )
    (net (code "111") (name "RS422_T4+") (class "Default")
      (node (ref "J2") (pin "27") (pinfunction "27_27") (pintype "unspecified"))
      (node (ref "U17") (pin "5") (pinfunction "Y_5") (pintype "output"))
    )
    (net (code "112") (name "RS422_T4-") (class "Default")
      (node (ref "J2") (pin "26") (pinfunction "26_26") (pintype "unspecified"))
      (node (ref "U17") (pin "6") (pinfunction "Z_6") (pintype "output"))
    )
    (net (code "113") (name "RS422_T5+") (class "Default")
      (node (ref "U18") (pin "5") (pinfunction "Y_5") (pintype "output"))
    )
    (net (code "114") (name "RS422_T5-") (class "Default")
      (node (ref "U18") (pin "6") (pinfunction "Z_6") (pintype "output"))
    )
    (net (code "115") (name "R{slash}W") (class "Default")
      (node (ref "U1") (pin "101") (pinfunction "IO,_LVDS39p,_DQ1R1_101") (pintype "bidirectional"))
      (node (ref "U5") (pin "20") (pinfunction "R/~W~_20") (pintype "unspecified"))
    )
    (net (code "116") (name "TCK") (class "Default")
      (node (ref "P1") (pin "1") (pinfunction "1_1") (pintype "unspecified"))
      (node (ref "RP2") (pin "5") (pinfunction "5_5") (pintype "unspecified"))
      (node (ref "U1") (pin "12") (pinfunction "TCK_12") (pintype "input"))
    )
    (net (code "117") (name "TDI") (class "Default")
      (node (ref "P1") (pin "9") (pinfunction "9_9") (pintype "unspecified"))
      (node (ref "RP2") (pin "8") (pinfunction "8_8") (pintype "unspecified"))
      (node (ref "U1") (pin "13") (pinfunction "TDI_13") (pintype "input"))
    )
    (net (code "118") (name "TDO") (class "Default")
      (node (ref "P1") (pin "3") (pinfunction "3_3") (pintype "unspecified"))
      (node (ref "U1") (pin "10") (pinfunction "TDO_10") (pintype "output"))
    )
    (net (code "119") (name "TMS") (class "Default")
      (node (ref "P1") (pin "5") (pinfunction "5_5") (pintype "unspecified"))
      (node (ref "RP2") (pin "6") (pinfunction "6_6") (pintype "unspecified"))
      (node (ref "U1") (pin "11") (pinfunction "TMS_11") (pintype "input"))
    )
    (net (code "120") (name "UART1.RXD") (class "Default")
      (node (ref "U1") (pin "103") (pinfunction "IO,_PLL2_OUTp,_DQ1R0_103") (pintype "bidirectional"))
      (node (ref "U12") (pin "2") (pinfunction "RO_2") (pintype "output"))
    )
    (net (code "121") (name "UART1.TXD") (class "Default")
      (node (ref "U1") (pin "92") (pinfunction "IO,_LVDS47n,_DQ1R6_92") (pintype "bidirectional"))
      (node (ref "U12") (pin "3") (pinfunction "DI_3") (pintype "input"))
    )
    (net (code "122") (name "UART2.RXD") (class "Default")
      (node (ref "U1") (pin "97") (pinfunction "IO,_LVDS45n,_DQ1R3_97") (pintype "bidirectional"))
    )
    (net (code "123") (name "UART2.TXD") (class "Default")
      (node (ref "U1") (pin "115") (pinfunction "IO,_LVDS36p_115") (pintype "bidirectional"))
    )
    (net (code "124") (name "UART3.RXD") (class "Default")
      (node (ref "U1") (pin "94") (pinfunction "IO,_LVDS46n,_DQ1R5_94") (pintype "bidirectional"))
    )
    (net (code "125") (name "UART3.TXD") (class "Default")
      (node (ref "U1") (pin "118") (pinfunction "IO,_LVDS34n_118") (pintype "bidirectional"))
    )
    (net (code "126") (name "UART4.RXD") (class "Default")
      (node (ref "U1") (pin "104") (pinfunction "IO,_PLL2_OUTn_104") (pintype "bidirectional"))
      (node (ref "U17") (pin "2") (pinfunction "RO_2") (pintype "output"))
    )
    (net (code "127") (name "UART4.TXD") (class "Default")
      (node (ref "U1") (pin "86") (pinfunction "IO,_LVDS48n,_DQ1R7_86") (pintype "bidirectional"))
      (node (ref "U17") (pin "3") (pinfunction "DI_3") (pintype "input"))
    )
    (net (code "128") (name "UART5.RXD") (class "Default")
      (node (ref "U18") (pin "2") (pinfunction "RO_2") (pintype "output"))
    )
    (net (code "129") (name "UART5.TXD") (class "Default")
      (node (ref "U18") (pin "3") (pinfunction "DI_3") (pintype "input"))
    )
    (net (code "130") (name "VCC+5V") (class "Default")
      (node (ref "C26") (pin "1") (pinfunction "1_1") (pintype "unspecified"))
      (node (ref "C27") (pin "1") (pinfunction "1_1") (pintype "unspecified"))
      (node (ref "C4") (pin "1") (pinfunction "1_1") (pintype "unspecified"))
      (node (ref "J2") (pin "37") (pinfunction "37_37") (pintype "unspecified"))
      (node (ref "J2") (pin "66") (pinfunction "66_66") (pintype "unspecified"))
      (node (ref "J2") (pin "67") (pinfunction "67_67") (pintype "unspecified"))
      (node (ref "J2") (pin "68") (pinfunction "68_68") (pintype "unspecified"))
      (node (ref "R12") (pin "2") (pinfunction "2_2") (pintype "unspecified"))
      (node (ref "R14") (pin "2") (pinfunction "2_2") (pintype "unspecified"))
      (node (ref "R21") (pin "1") (pinfunction "1_1") (pintype "unspecified"))
      (node (ref "R22") (pin "1") (pinfunction "1_1") (pintype "unspecified"))
      (node (ref "R24") (pin "1") (pinfunction "1_1") (pintype "unspecified"))
      (node (ref "R25") (pin "1") (pinfunction "1_1") (pintype "unspecified"))
      (node (ref "U11") (pin "2") (pinfunction "VI_2") (pintype "unspecified"))
      (node (ref "U19") (pin "1") (pinfunction "Vi+_1") (pintype "unspecified"))
    )
    (net (code "131") (name "VCCINT") (class "Default")
      (node (ref "C15") (pin "2") (pinfunction "2_2") (pintype "unspecified"))
      (node (ref "C16") (pin "2") (pinfunction "2_2") (pintype "unspecified"))
      (node (ref "C17") (pin "2") (pinfunction "2_2") (pintype "unspecified"))
      (node (ref "C18") (pin "2") (pinfunction "2_2") (pintype "unspecified"))
      (node (ref "C19") (pin "2") (pinfunction "2_2") (pintype "unspecified"))
      (node (ref "C20") (pin "2") (pinfunction "2_2") (pintype "unspecified"))
      (node (ref "C21") (pin "1") (pinfunction "1_1") (pintype "unspecified"))
      (node (ref "C22") (pin "2") (pinfunction "2_2") (pintype "unspecified"))
      (node (ref "C23") (pin "2") (pinfunction "2_2") (pintype "unspecified"))
      (node (ref "C24") (pin "2") (pinfunction "2_2") (pintype "unspecified"))
      (node (ref "C25") (pin "2") (pinfunction "2_2") (pintype "unspecified"))
      (node (ref "U1") (pin "107") (pinfunction "VCCD_PLL2_107") (pintype "unspecified"))
      (node (ref "U1") (pin "109") (pinfunction "VCCA_PLL2_109") (pintype "unspecified"))
      (node (ref "U1") (pin "124") (pinfunction "VCCINT_124") (pintype "unspecified"))
      (node (ref "U1") (pin "131") (pinfunction "VCCINT_131") (pintype "unspecified"))
      (node (ref "U1") (pin "26") (pinfunction "VCCINT_26") (pintype "unspecified"))
      (node (ref "U1") (pin "35") (pinfunction "VCCD_PLL1_35") (pintype "unspecified"))
      (node (ref "U1") (pin "37") (pinfunction "VCCA_PLL1_37") (pintype "unspecified"))
      (node (ref "U1") (pin "50") (pinfunction "VCCINT_50") (pintype "unspecified"))
      (node (ref "U1") (pin "62") (pinfunction "VCCINT_62") (pintype "unspecified"))
      (node (ref "U1") (pin "81") (pinfunction "VCCINT_81") (pintype "unspecified"))
      (node (ref "U10") (pin "4") (pinfunction "OUT_4") (pintype "unspecified"))
    )
    (net (code "132") (name "VOUTA") (class "Default")
      (node (ref "J2") (pin "2") (pinfunction "2_2") (pintype "unspecified"))
      (node (ref "U5") (pin "3") (pinfunction "VOUTA_3") (pintype "unspecified"))
    )
    (net (code "133") (name "VOUTB") (class "Default")
      (node (ref "J2") (pin "4") (pinfunction "4_4") (pintype "unspecified"))
      (node (ref "U5") (pin "2") (pinfunction "VOUTB_2") (pintype "unspecified"))
    )
    (net (code "134") (name "unconnected-(J2-Pad10)") (class "Default")
      (node (ref "J2") (pin "10") (pinfunction "10_10") (pintype "unspecified"))
    )
    (net (code "135") (name "unconnected-(J2-Pad11)") (class "Default")
      (node (ref "J2") (pin "11") (pinfunction "11_11") (pintype "unspecified"))
    )
    (net (code "136") (name "unconnected-(J2-Pad12)") (class "Default")
      (node (ref "J2") (pin "12") (pinfunction "12_12") (pintype "unspecified"))
    )
    (net (code "137") (name "unconnected-(J2-Pad13)") (class "Default")
      (node (ref "J2") (pin "13") (pinfunction "13_13") (pintype "unspecified"))
    )
    (net (code "138") (name "unconnected-(J2-Pad14)") (class "Default")
      (node (ref "J2") (pin "14") (pinfunction "14_14") (pintype "unspecified"))
    )
    (net (code "139") (name "unconnected-(J2-Pad15)") (class "Default")
      (node (ref "J2") (pin "15") (pinfunction "15_15") (pintype "unspecified"))
    )
    (net (code "140") (name "unconnected-(J2-Pad16)") (class "Default")
      (node (ref "J2") (pin "16") (pinfunction "16_16") (pintype "unspecified"))
    )
    (net (code "141") (name "unconnected-(J2-Pad17)") (class "Default")
      (node (ref "J2") (pin "17") (pinfunction "17_17") (pintype "unspecified"))
    )
    (net (code "142") (name "unconnected-(J2-Pad38)") (class "Default")
      (node (ref "J2") (pin "38") (pinfunction "38_38") (pintype "unspecified"))
    )
    (net (code "143") (name "unconnected-(J2-Pad41)") (class "Default")
      (node (ref "J2") (pin "41") (pinfunction "41_41") (pintype "unspecified"))
    )
    (net (code "144") (name "unconnected-(J2-Pad42)") (class "Default")
      (node (ref "J2") (pin "42") (pinfunction "42_42") (pintype "unspecified"))
    )
    (net (code "145") (name "unconnected-(J2-Pad43)") (class "Default")
      (node (ref "J2") (pin "43") (pinfunction "43_43") (pintype "unspecified"))
    )
    (net (code "146") (name "unconnected-(J2-Pad44)") (class "Default")
      (node (ref "J2") (pin "44") (pinfunction "44_44") (pintype "unspecified"))
    )
    (net (code "147") (name "unconnected-(J2-Pad45)") (class "Default")
      (node (ref "J2") (pin "45") (pinfunction "45_45") (pintype "unspecified"))
    )
    (net (code "148") (name "unconnected-(J2-Pad46)") (class "Default")
      (node (ref "J2") (pin "46") (pinfunction "46_46") (pintype "unspecified"))
    )
    (net (code "149") (name "unconnected-(J2-Pad47)") (class "Default")
      (node (ref "J2") (pin "47") (pinfunction "47_47") (pintype "unspecified"))
    )
    (net (code "150") (name "unconnected-(J2-Pad48)") (class "Default")
      (node (ref "J2") (pin "48") (pinfunction "48_48") (pintype "unspecified"))
    )
    (net (code "151") (name "unconnected-(J2-Pad49)") (class "Default")
      (node (ref "J2") (pin "49") (pinfunction "49_49") (pintype "unspecified"))
    )
    (net (code "152") (name "unconnected-(J2-Pad50)") (class "Default")
      (node (ref "J2") (pin "50") (pinfunction "50_50") (pintype "unspecified"))
    )
    (net (code "153") (name "unconnected-(J2-Pad53)") (class "Default")
      (node (ref "J2") (pin "53") (pinfunction "53_53") (pintype "unspecified"))
    )
    (net (code "154") (name "unconnected-(J2-Pad54)") (class "Default")
      (node (ref "J2") (pin "54") (pinfunction "54_54") (pintype "unspecified"))
    )
    (net (code "155") (name "unconnected-(J2-Pad55)") (class "Default")
      (node (ref "J2") (pin "55") (pinfunction "55_55") (pintype "unspecified"))
    )
    (net (code "156") (name "unconnected-(J2-Pad56)") (class "Default")
      (node (ref "J2") (pin "56") (pinfunction "56_56") (pintype "unspecified"))
    )
    (net (code "157") (name "unconnected-(J2-Pad57)") (class "Default")
      (node (ref "J2") (pin "57") (pinfunction "57_57") (pintype "unspecified"))
    )
    (net (code "158") (name "unconnected-(J2-Pad58)") (class "Default")
      (node (ref "J2") (pin "58") (pinfunction "58_58") (pintype "unspecified"))
    )
    (net (code "159") (name "unconnected-(J2-Pad59)") (class "Default")
      (node (ref "J2") (pin "59") (pinfunction "59_59") (pintype "unspecified"))
    )
    (net (code "160") (name "unconnected-(P1-Pad7)") (class "Default")
      (node (ref "P1") (pin "7") (pinfunction "7_7") (pintype "unspecified+no_connect"))
    )
    (net (code "161") (name "unconnected-(P1-Pad8)") (class "Default")
      (node (ref "P1") (pin "8") (pinfunction "8_8") (pintype "unspecified+no_connect"))
    )
    (net (code "162") (name "unconnected-(RP2-Pad2)") (class "Default")
      (node (ref "RP2") (pin "2") (pinfunction "2_2") (pintype "unspecified+no_connect"))
    )
    (net (code "163") (name "unconnected-(RP2-Pad7)") (class "Default")
      (node (ref "RP2") (pin "7") (pinfunction "7_7") (pintype "unspecified+no_connect"))
    )
    (net (code "164") (name "unconnected-(U1H-IO,_LVDS46p,_DQ1R4-Pad96)") (class "Default")
      (node (ref "U1") (pin "96") (pinfunction "IO,_LVDS46p,_DQ1R4_96") (pintype "bidirectional"))
    )
    (net (code "165") (name "unconnected-(U1H-IO,_LVDS47p,_(DPCLK7{slash}DQS0R)-Pad93)") (class "Default")
      (node (ref "U1") (pin "93") (pinfunction "IO,_LVDS47p,_(DPCLK7/DQS0R)_93") (pintype "bidirectional"))
    )
    (net (code "166") (name "unconnected-(U1I-IO,_LVDS37p-Pad113)") (class "Default")
      (node (ref "U1") (pin "113") (pinfunction "IO,_LVDS37p_113") (pintype "bidirectional"))
    )
    (net (code "167") (name "unconnected-(U3-Pad1)") (class "Default")
      (node (ref "U3") (pin "1") (pintype "unspecified+no_connect"))
    )
    (net (code "168") (name "unconnected-(U4-NC-Pad3)") (class "Default")
      (node (ref "U4") (pin "3") (pinfunction "NC_3") (pintype "unspecified+no_connect"))
    )
    (net (code "169") (name "unconnected-(U4-NC-Pad4)") (class "Default")
      (node (ref "U4") (pin "4") (pinfunction "NC_4") (pintype "unspecified+no_connect"))
    )
    (net (code "170") (name "unconnected-(U4-NC-Pad5)") (class "Default")
      (node (ref "U4") (pin "5") (pinfunction "NC_5") (pintype "unspecified+no_connect"))
    )
    (net (code "171") (name "unconnected-(U4-NC-Pad6)") (class "Default")
      (node (ref "U4") (pin "6") (pinfunction "NC_6") (pintype "unspecified+no_connect"))
    )
    (net (code "172") (name "unconnected-(U4-NC-Pad11)") (class "Default")
      (node (ref "U4") (pin "11") (pinfunction "NC_11") (pintype "unspecified+no_connect"))
    )
    (net (code "173") (name "unconnected-(U4-NC-Pad12)") (class "Default")
      (node (ref "U4") (pin "12") (pinfunction "NC_12") (pintype "unspecified+no_connect"))
    )
    (net (code "174") (name "unconnected-(U4-NC-Pad13)") (class "Default")
      (node (ref "U4") (pin "13") (pinfunction "NC_13") (pintype "unspecified+no_connect"))
    )
    (net (code "175") (name "unconnected-(U4-NC-Pad14)") (class "Default")
      (node (ref "U4") (pin "14") (pinfunction "NC_14") (pintype "unspecified+no_connect"))
    )
    (net (code "176") (name "unconnected-(U5-VLOGIC-Pad24)") (class "Default")
      (node (ref "U5") (pin "24") (pinfunction "VLOGIC_24") (pintype "unspecified+no_connect"))
    )
  )
)
